# trill.net
KiCad netlist of a schematic drawn in EAGLE
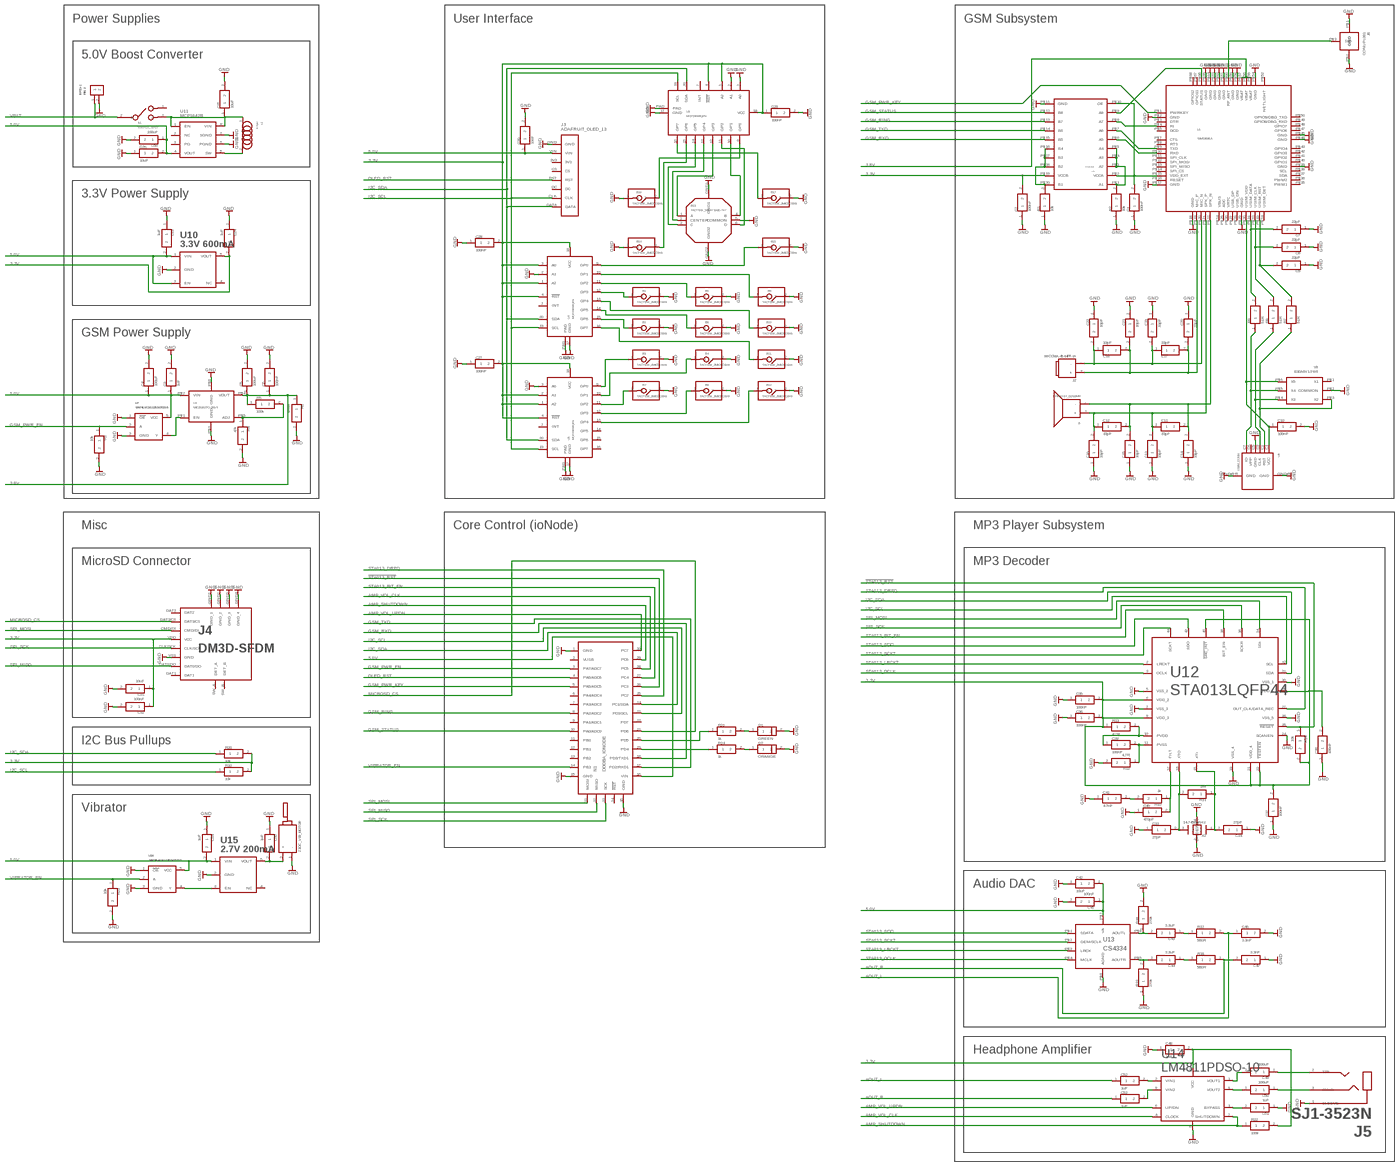
[diagram p0: schematic, sheet 1, overview]
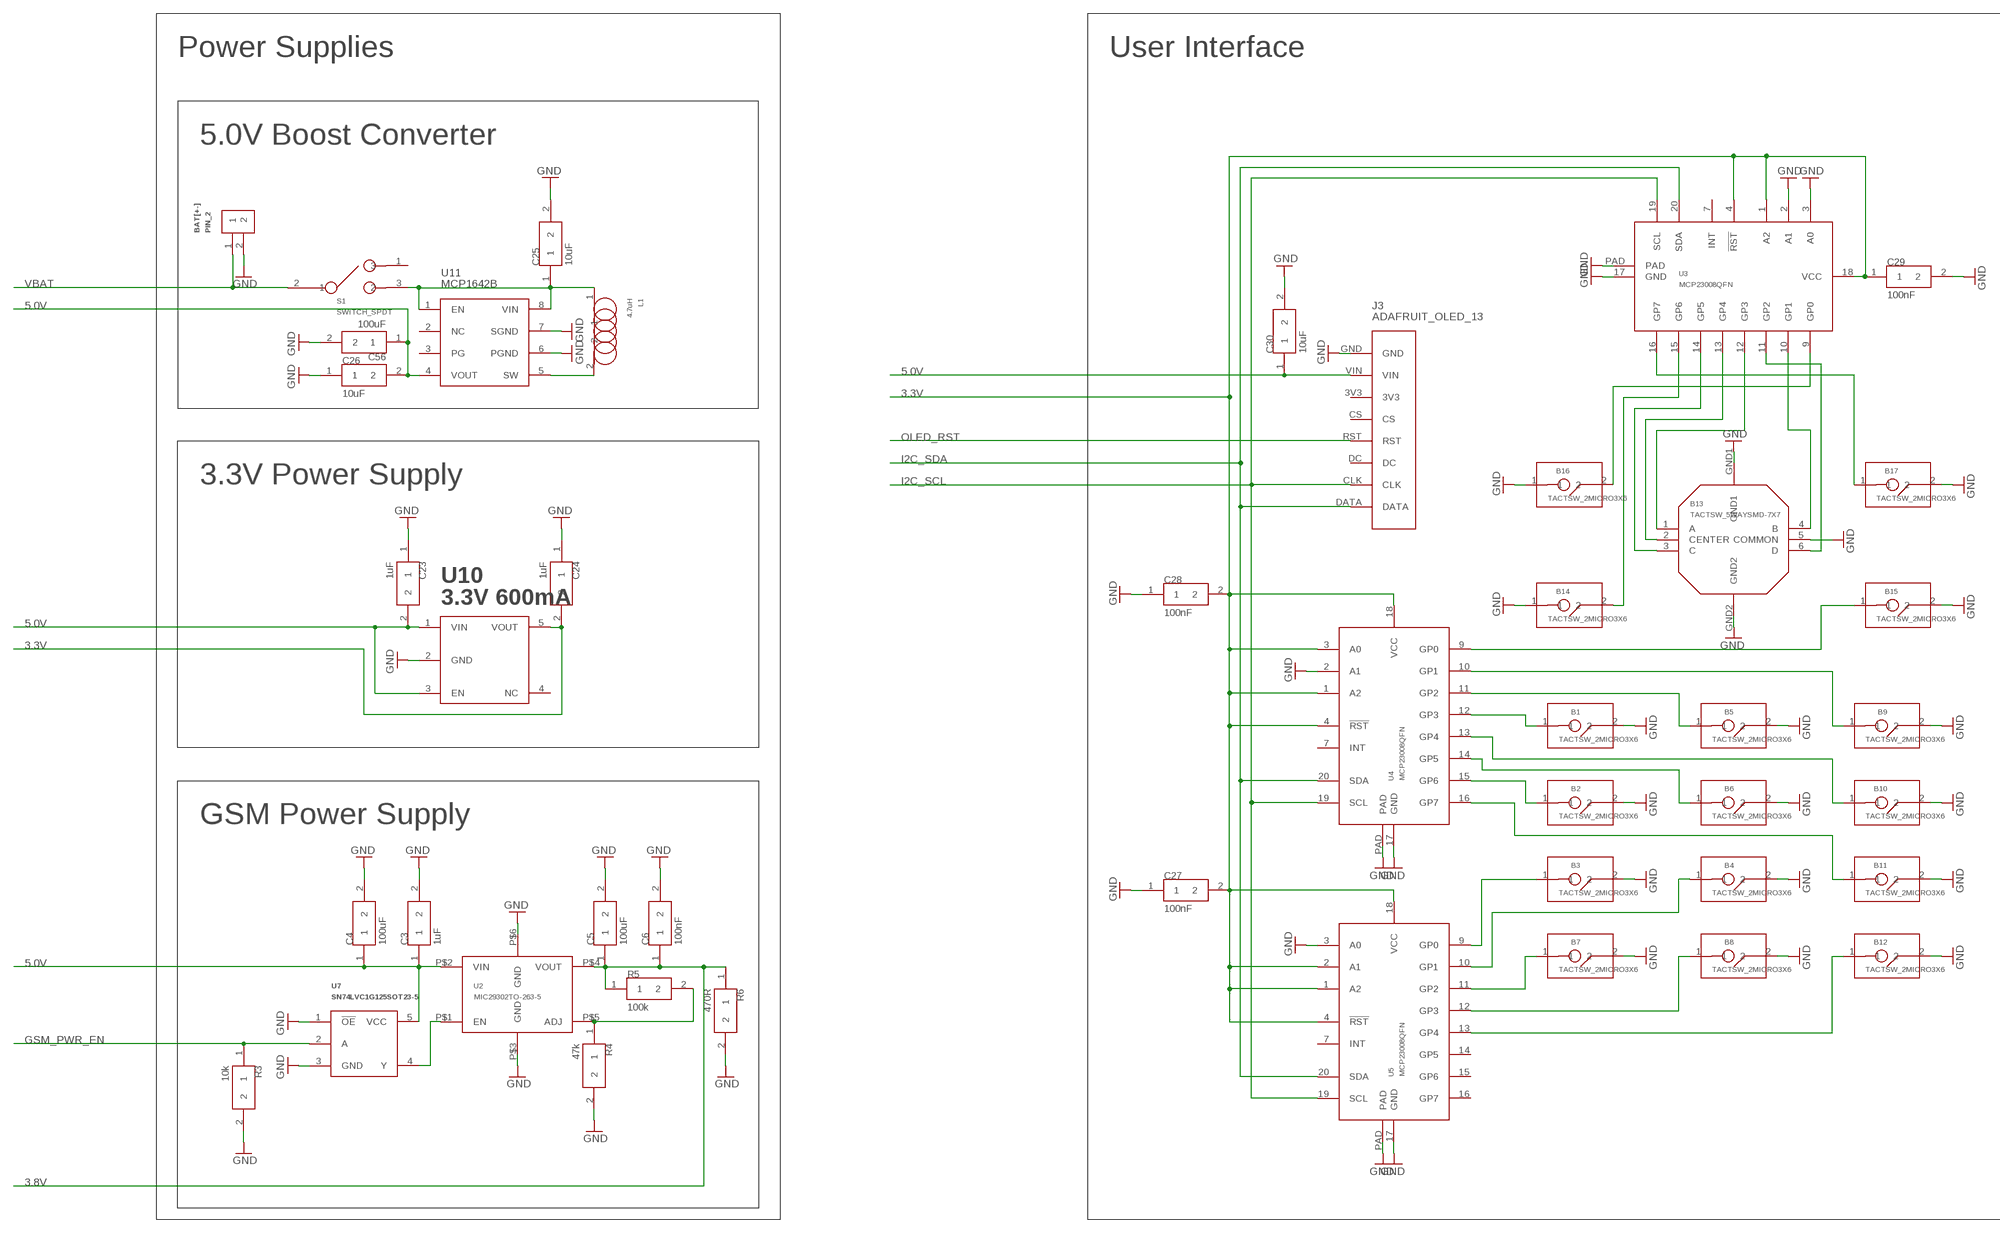
[diagram p1: schematic, sheet 1, part 1 of 4]
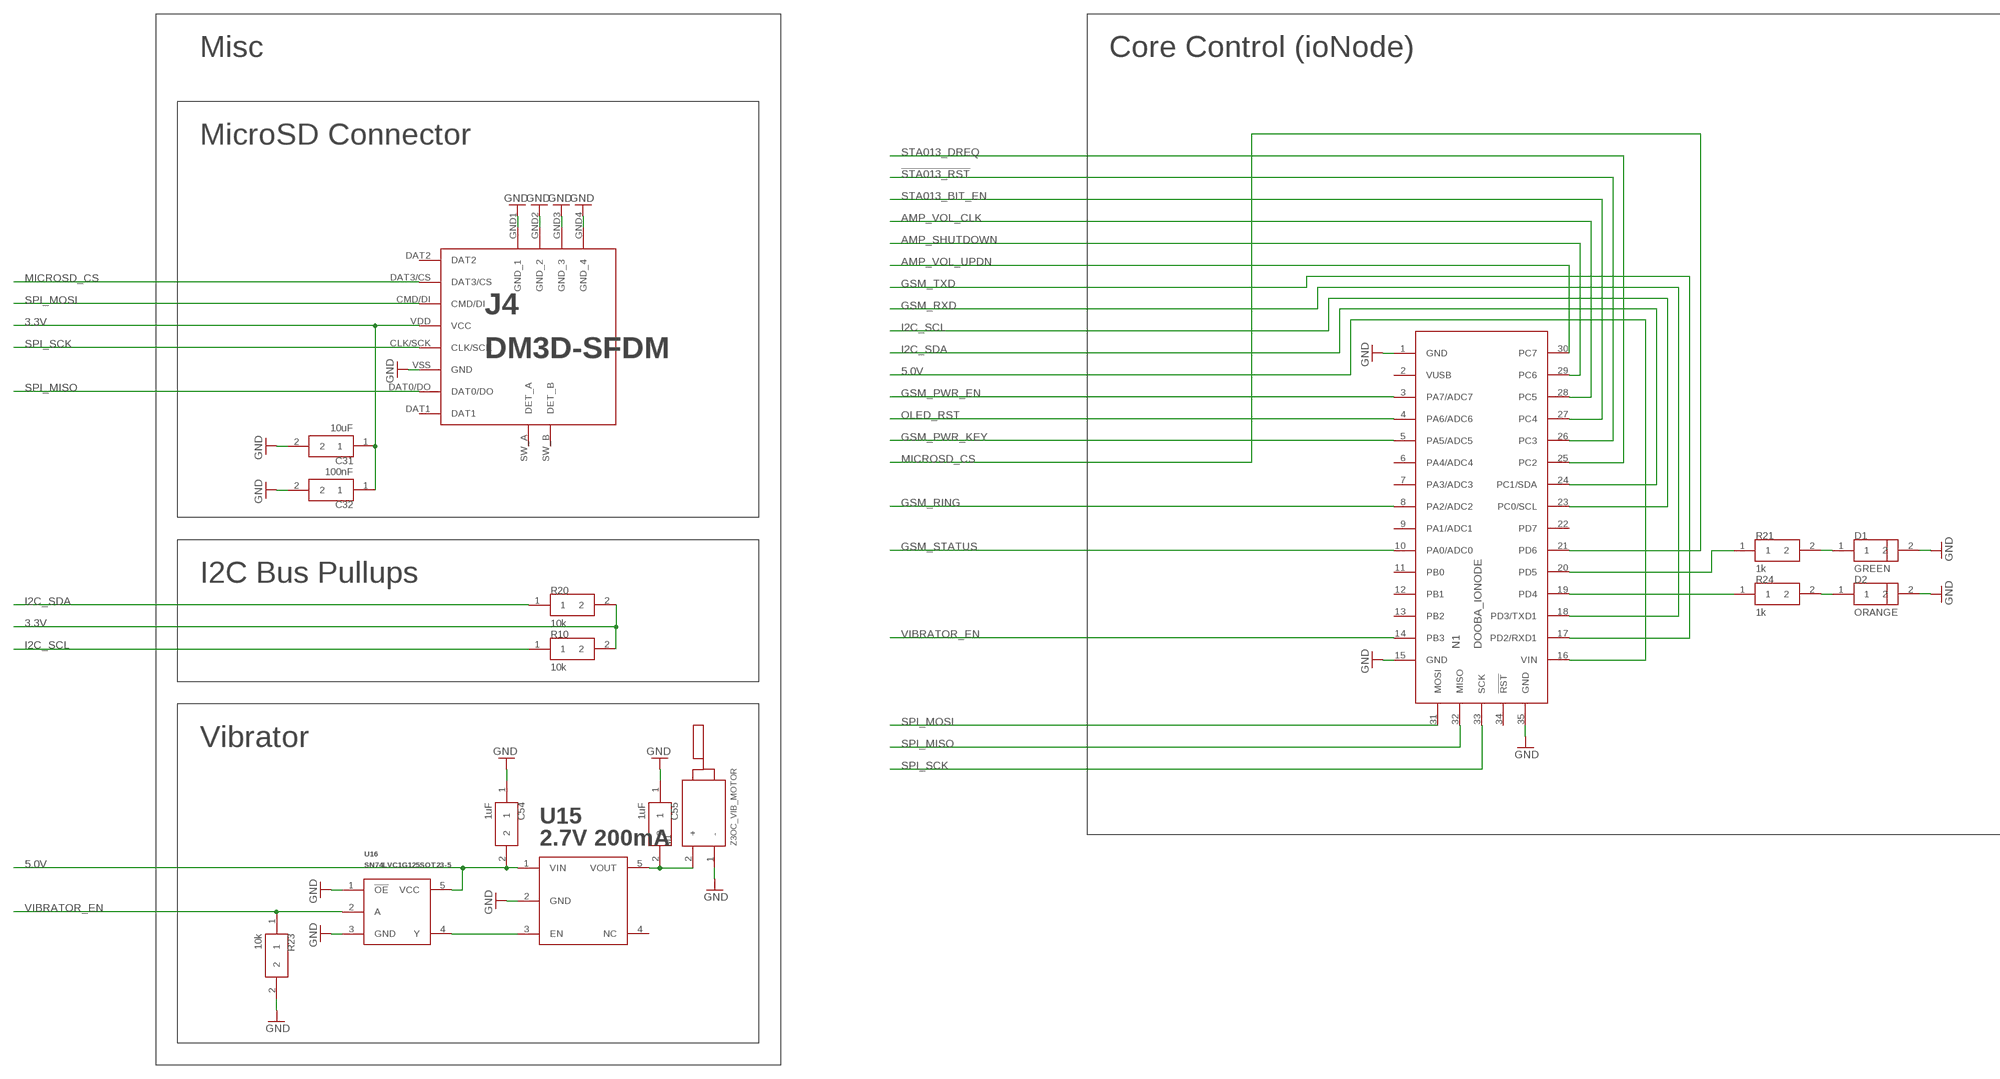
[diagram p2: schematic, sheet 1, part 2 of 4]
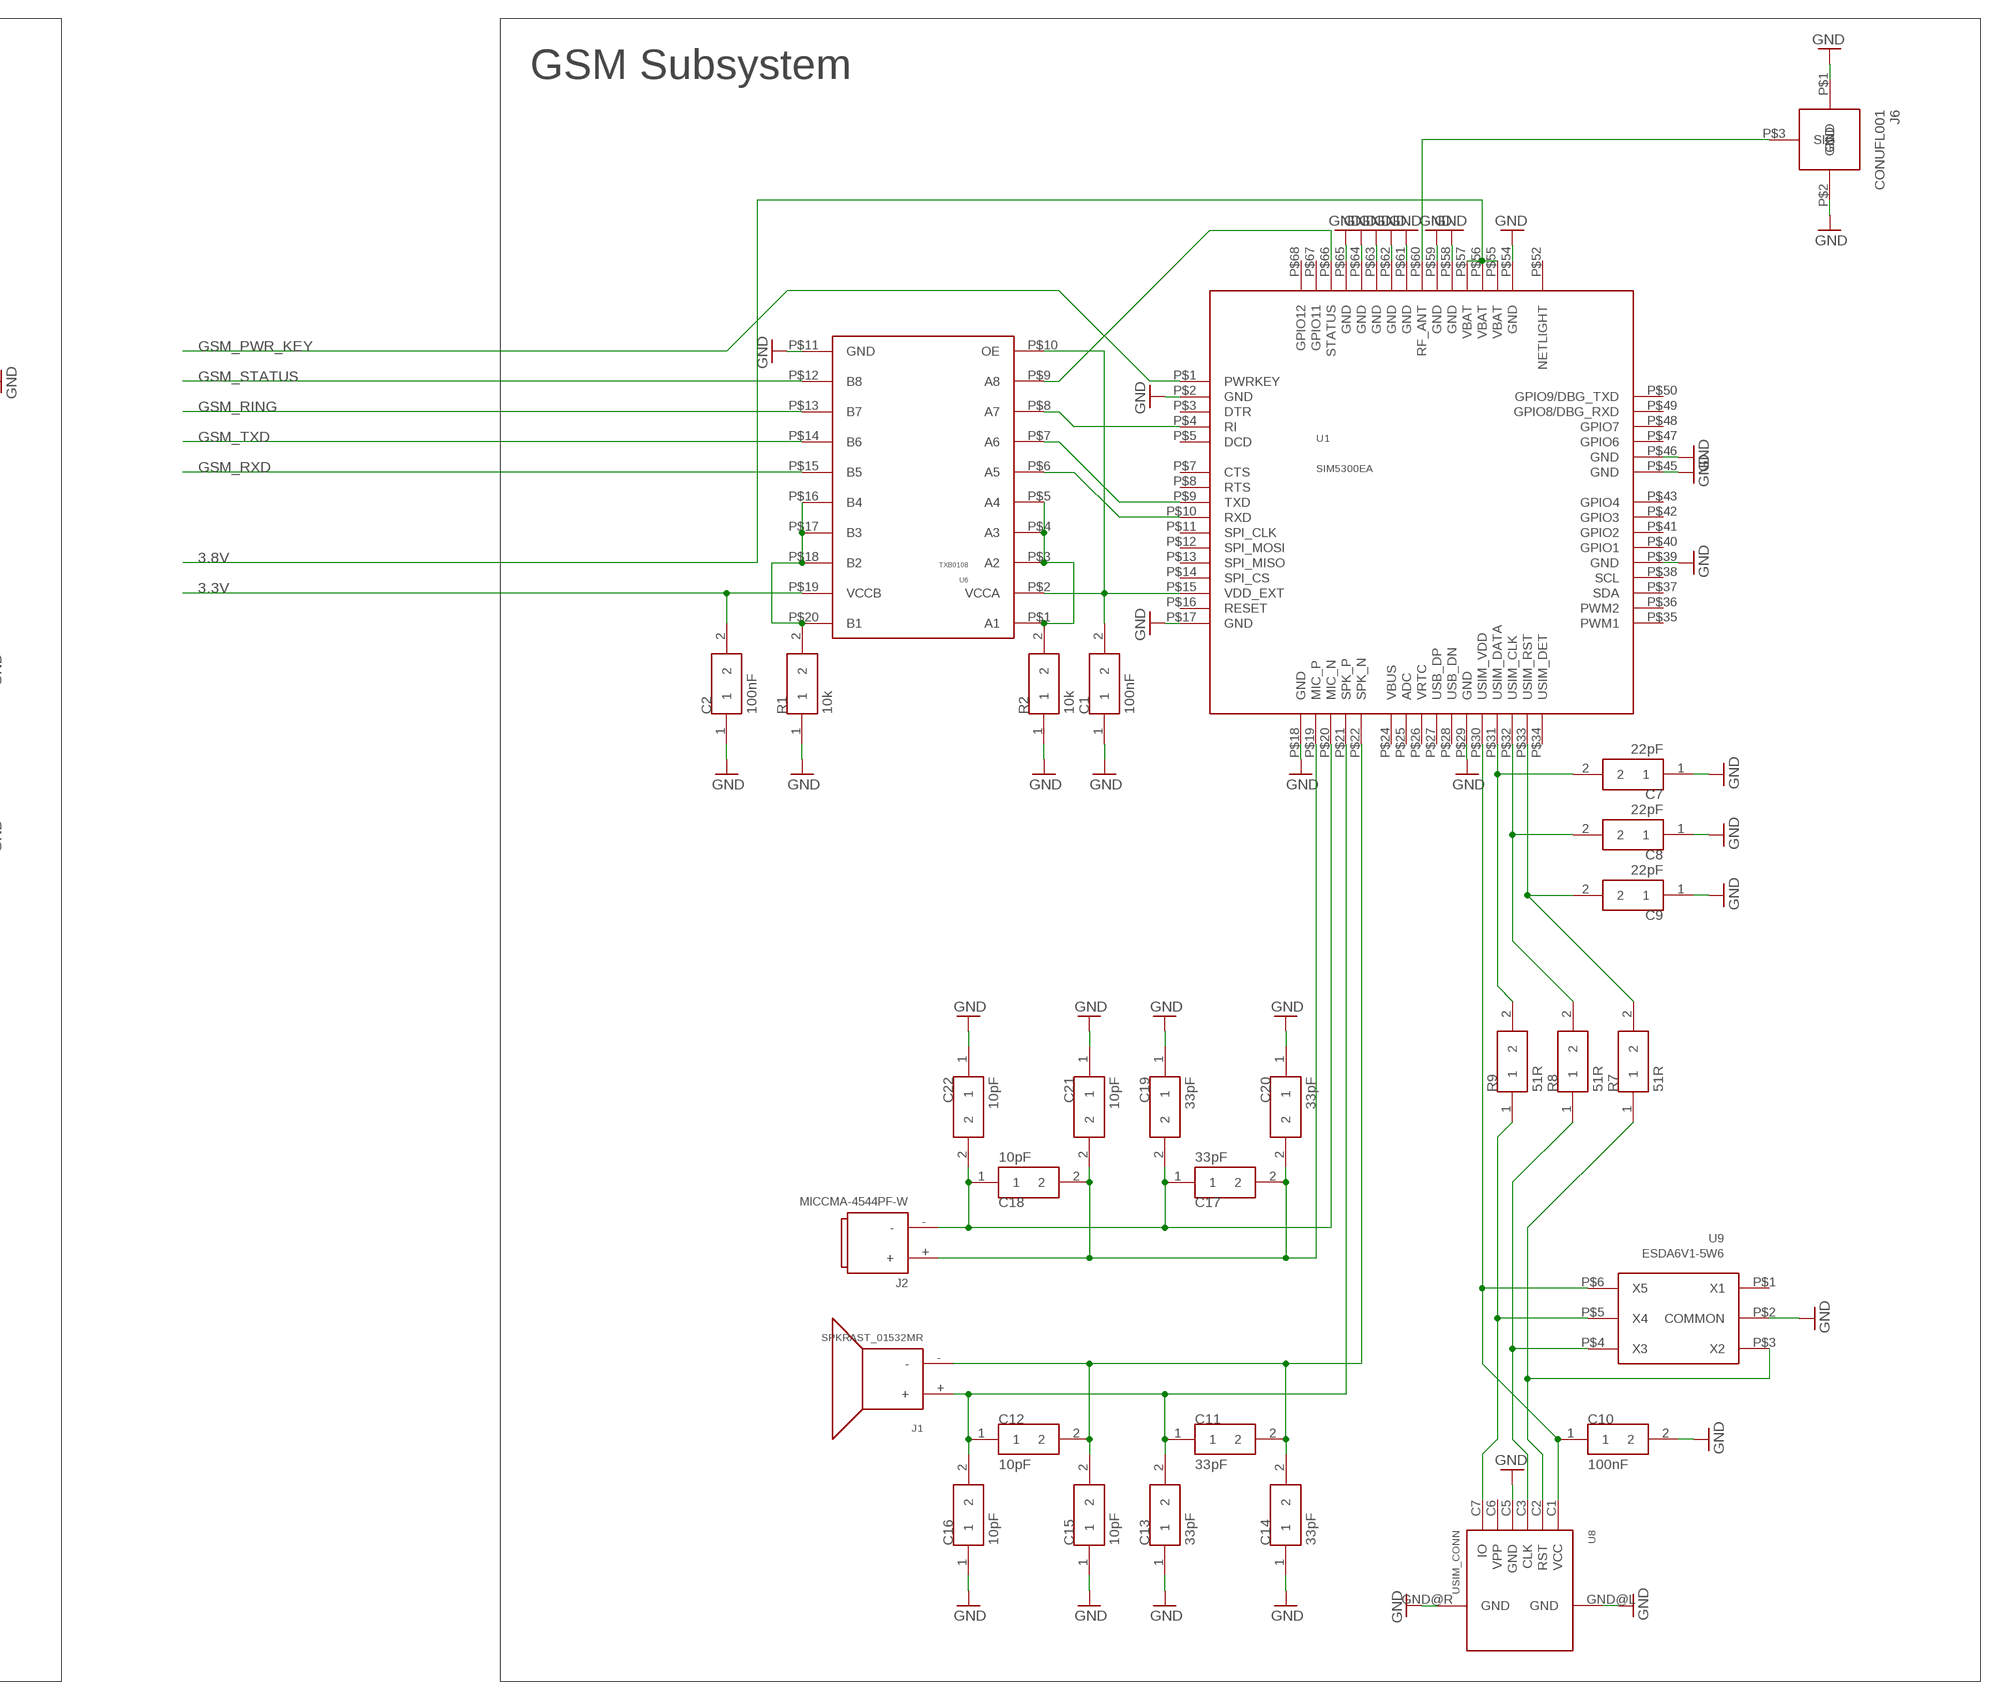
[diagram p3: schematic, sheet 1, part 3 of 4]
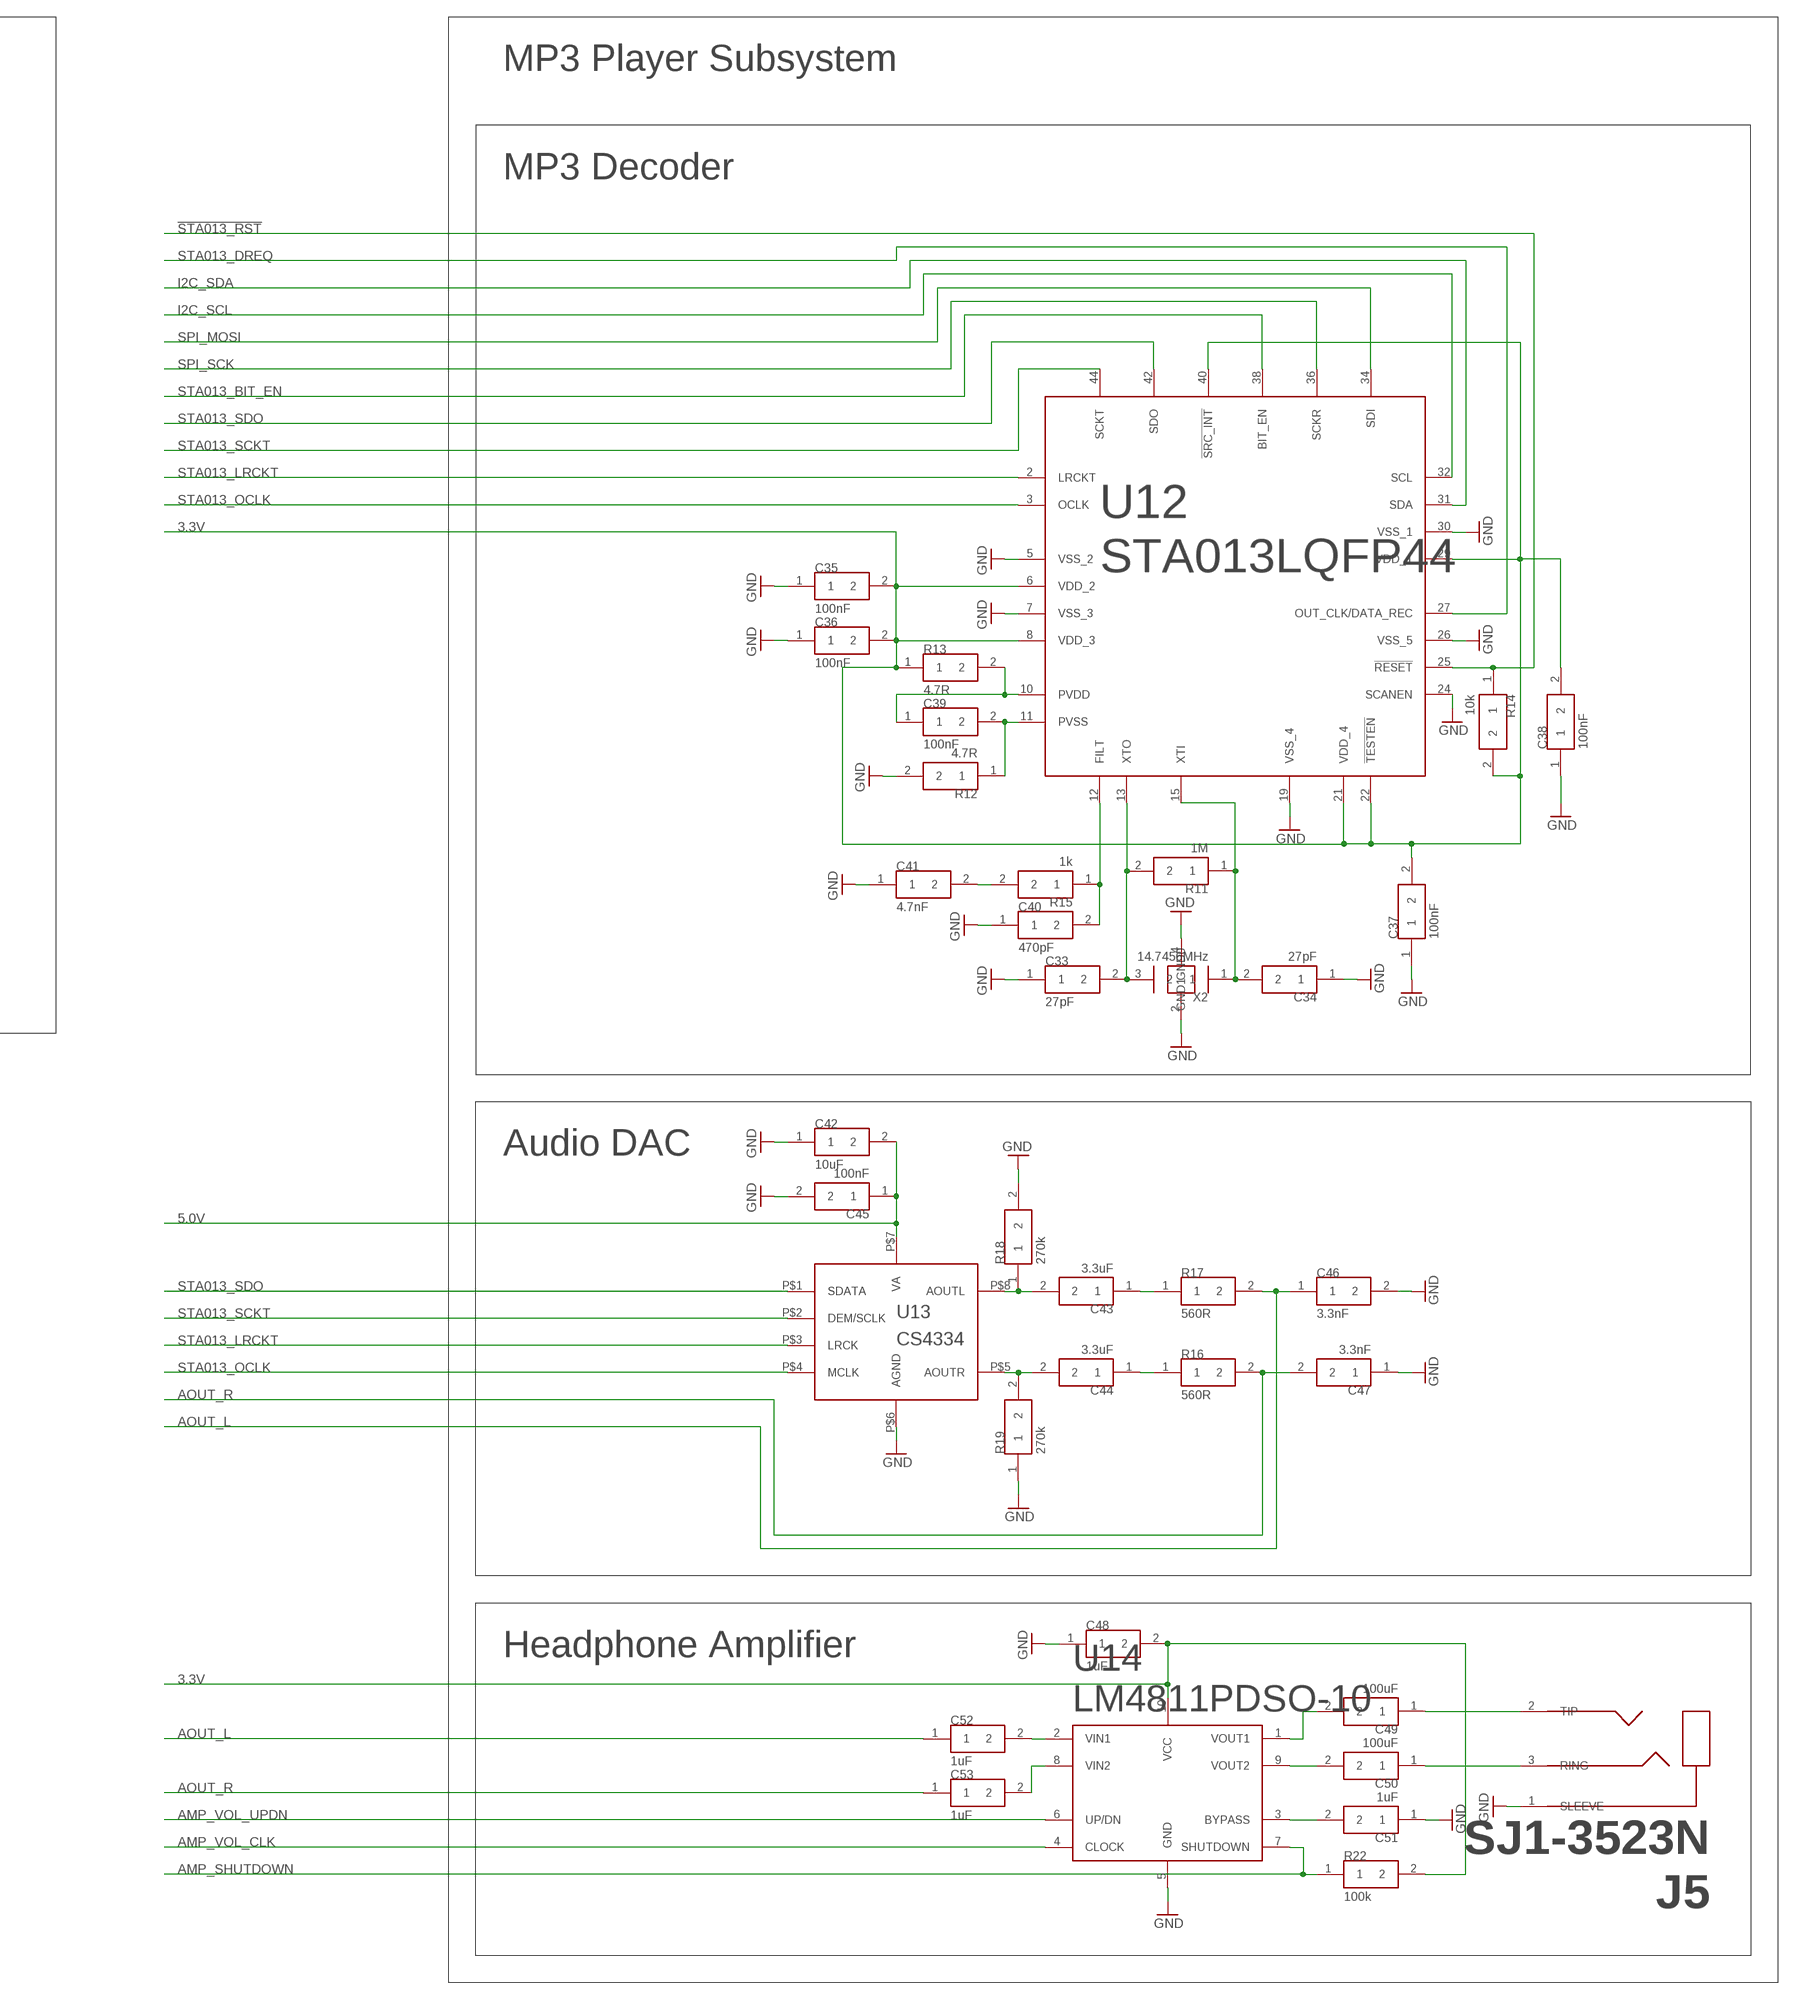
[diagram p4: schematic, sheet 1, part 4 of 4]

(export (version "E")
  (design (tool "Eeschema 10.0.6"))
  (components
    (comp (ref "B1")
      (value "TACTSW_2MICRO3X6")
      (footprint "eagle-import:TACTSW_MICRO3X6")
      (libsource (lib "eagle-import") (part "TACTSW_2MICRO3X6"))
    )
    (comp (ref "B2")
      (value "TACTSW_2MICRO3X6")
      (footprint "eagle-import:TACTSW_MICRO3X6")
      (libsource (lib "eagle-import") (part "TACTSW_2MICRO3X6"))
    )
    (comp (ref "B3")
      (value "TACTSW_2MICRO3X6")
      (footprint "eagle-import:TACTSW_MICRO3X6")
      (libsource (lib "eagle-import") (part "TACTSW_2MICRO3X6"))
    )
    (comp (ref "B4")
      (value "TACTSW_2MICRO3X6")
      (footprint "eagle-import:TACTSW_MICRO3X6")
      (libsource (lib "eagle-import") (part "TACTSW_2MICRO3X6"))
    )
    (comp (ref "B5")
      (value "TACTSW_2MICRO3X6")
      (footprint "eagle-import:TACTSW_MICRO3X6")
      (libsource (lib "eagle-import") (part "TACTSW_2MICRO3X6"))
    )
    (comp (ref "B6")
      (value "TACTSW_2MICRO3X6")
      (footprint "eagle-import:TACTSW_MICRO3X6")
      (libsource (lib "eagle-import") (part "TACTSW_2MICRO3X6"))
    )
    (comp (ref "B7")
      (value "TACTSW_2MICRO3X6")
      (footprint "eagle-import:TACTSW_MICRO3X6")
      (libsource (lib "eagle-import") (part "TACTSW_2MICRO3X6"))
    )
    (comp (ref "B8")
      (value "TACTSW_2MICRO3X6")
      (footprint "eagle-import:TACTSW_MICRO3X6")
      (libsource (lib "eagle-import") (part "TACTSW_2MICRO3X6"))
    )
    (comp (ref "B9")
      (value "TACTSW_2MICRO3X6")
      (footprint "eagle-import:TACTSW_MICRO3X6")
      (libsource (lib "eagle-import") (part "TACTSW_2MICRO3X6"))
    )
    (comp (ref "B10")
      (value "TACTSW_2MICRO3X6")
      (footprint "eagle-import:TACTSW_MICRO3X6")
      (libsource (lib "eagle-import") (part "TACTSW_2MICRO3X6"))
    )
    (comp (ref "B11")
      (value "TACTSW_2MICRO3X6")
      (footprint "eagle-import:TACTSW_MICRO3X6")
      (libsource (lib "eagle-import") (part "TACTSW_2MICRO3X6"))
    )
    (comp (ref "B12")
      (value "TACTSW_2MICRO3X6")
      (footprint "eagle-import:TACTSW_MICRO3X6")
      (libsource (lib "eagle-import") (part "TACTSW_2MICRO3X6"))
    )
    (comp (ref "B13")
      (value "TACTSW_5WAYSMD-7X7")
      (footprint "eagle-import:TACTSW-5WAY-7X7")
      (libsource (lib "eagle-import") (part "TACTSW_5WAYSMD-7X7"))
    )
    (comp (ref "B14")
      (value "TACTSW_2MICRO3X6")
      (footprint "eagle-import:TACTSW_MICRO3X6")
      (libsource (lib "eagle-import") (part "TACTSW_2MICRO3X6"))
    )
    (comp (ref "B15")
      (value "TACTSW_2MICRO3X6")
      (footprint "eagle-import:TACTSW_MICRO3X6")
      (libsource (lib "eagle-import") (part "TACTSW_2MICRO3X6"))
    )
    (comp (ref "B16")
      (value "TACTSW_2MICRO3X6")
      (footprint "eagle-import:TACTSW_MICRO3X6")
      (libsource (lib "eagle-import") (part "TACTSW_2MICRO3X6"))
    )
    (comp (ref "B17")
      (value "TACTSW_2MICRO3X6")
      (footprint "eagle-import:TACTSW_MICRO3X6")
      (libsource (lib "eagle-import") (part "TACTSW_2MICRO3X6"))
    )
    (comp (ref "BAT[+-]")
      (value "PIN_2")
      (footprint "eagle-import:PIN_2")
      (libsource (lib "eagle-import") (part "PIN_2"))
    )
    (comp (ref "C1")
      (value "100nF")
      (footprint "eagle-import:0805")
      (libsource (lib "eagle-import") (part "CAP0805"))
    )
    (comp (ref "C2")
      (value "100nF")
      (footprint "eagle-import:0805")
      (libsource (lib "eagle-import") (part "CAP0805"))
    )
    (comp (ref "C3")
      (value "1uF")
      (footprint "eagle-import:0805")
      (libsource (lib "eagle-import") (part "CAP0805"))
    )
    (comp (ref "C4")
      (value "100uF")
      (footprint "eagle-import:1210")
      (libsource (lib "eagle-import") (part "CAP1210"))
    )
    (comp (ref "C5")
      (value "100uF")
      (footprint "eagle-import:1210")
      (libsource (lib "eagle-import") (part "CAP1210"))
    )
    (comp (ref "C6")
      (value "100nF")
      (footprint "eagle-import:0805")
      (libsource (lib "eagle-import") (part "CAP0805"))
    )
    (comp (ref "C7")
      (value "22pF")
      (footprint "eagle-import:0805")
      (libsource (lib "eagle-import") (part "CAP0805"))
    )
    (comp (ref "C8")
      (value "22pF")
      (footprint "eagle-import:0805")
      (libsource (lib "eagle-import") (part "CAP0805"))
    )
    (comp (ref "C9")
      (value "22pF")
      (footprint "eagle-import:0805")
      (libsource (lib "eagle-import") (part "CAP0805"))
    )
    (comp (ref "C10")
      (value "100nF")
      (footprint "eagle-import:0805")
      (libsource (lib "eagle-import") (part "CAP0805"))
    )
    (comp (ref "C11")
      (value "33pF")
      (footprint "eagle-import:0805")
      (libsource (lib "eagle-import") (part "CAP0805"))
    )
    (comp (ref "C12")
      (value "10pF")
      (footprint "eagle-import:0805")
      (libsource (lib "eagle-import") (part "CAP0805"))
    )
    (comp (ref "C13")
      (value "33pF")
      (footprint "eagle-import:0805")
      (libsource (lib "eagle-import") (part "CAP0805"))
    )
    (comp (ref "C14")
      (value "33pF")
      (footprint "eagle-import:0805")
      (libsource (lib "eagle-import") (part "CAP0805"))
    )
    (comp (ref "C15")
      (value "10pF")
      (footprint "eagle-import:0805")
      (libsource (lib "eagle-import") (part "CAP0805"))
    )
    (comp (ref "C16")
      (value "10pF")
      (footprint "eagle-import:0805")
      (libsource (lib "eagle-import") (part "CAP0805"))
    )
    (comp (ref "C17")
      (value "33pF")
      (footprint "eagle-import:0805")
      (libsource (lib "eagle-import") (part "CAP0805"))
    )
    (comp (ref "C18")
      (value "10pF")
      (footprint "eagle-import:0805")
      (libsource (lib "eagle-import") (part "CAP0805"))
    )
    (comp (ref "C19")
      (value "33pF")
      (footprint "eagle-import:0805")
      (libsource (lib "eagle-import") (part "CAP0805"))
    )
    (comp (ref "C20")
      (value "33pF")
      (footprint "eagle-import:0805")
      (libsource (lib "eagle-import") (part "CAP0805"))
    )
    (comp (ref "C21")
      (value "10pF")
      (footprint "eagle-import:0805")
      (libsource (lib "eagle-import") (part "CAP0805"))
    )
    (comp (ref "C22")
      (value "10pF")
      (footprint "eagle-import:0805")
      (libsource (lib "eagle-import") (part "CAP0805"))
    )
    (comp (ref "C23")
      (value "1uF")
      (footprint "eagle-import:0805")
      (libsource (lib "eagle-import") (part "CAP0805"))
    )
    (comp (ref "C24")
      (value "1uF")
      (footprint "eagle-import:0805")
      (libsource (lib "eagle-import") (part "CAP0805"))
    )
    (comp (ref "C25")
      (value "10uF")
      (footprint "eagle-import:0805")
      (libsource (lib "eagle-import") (part "CAP0805"))
    )
    (comp (ref "C26")
      (value "10uF")
      (footprint "eagle-import:0805")
      (libsource (lib "eagle-import") (part "CAP0805"))
    )
    (comp (ref "C27")
      (value "100nF")
      (footprint "eagle-import:0805")
      (libsource (lib "eagle-import") (part "CAP0805"))
    )
    (comp (ref "C28")
      (value "100nF")
      (footprint "eagle-import:0805")
      (libsource (lib "eagle-import") (part "CAP0805"))
    )
    (comp (ref "C29")
      (value "100nF")
      (footprint "eagle-import:0805")
      (libsource (lib "eagle-import") (part "CAP0805"))
    )
    (comp (ref "C30")
      (value "10uF")
      (footprint "eagle-import:0805")
      (libsource (lib "eagle-import") (part "CAP0805"))
    )
    (comp (ref "C31")
      (value "10uF")
      (footprint "eagle-import:0805")
      (libsource (lib "eagle-import") (part "CAP0805"))
    )
    (comp (ref "C32")
      (value "100nF")
      (footprint "eagle-import:0805")
      (libsource (lib "eagle-import") (part "CAP0805"))
    )
    (comp (ref "C33")
      (value "27pF")
      (footprint "eagle-import:0805")
      (libsource (lib "eagle-import") (part "CAP0805"))
    )
    (comp (ref "C34")
      (value "27pF")
      (footprint "eagle-import:0805")
      (libsource (lib "eagle-import") (part "CAP0805"))
    )
    (comp (ref "C35")
      (value "100nF")
      (footprint "eagle-import:0805")
      (libsource (lib "eagle-import") (part "CAP0805"))
    )
    (comp (ref "C36")
      (value "100nF")
      (footprint "eagle-import:0805")
      (libsource (lib "eagle-import") (part "CAP0805"))
    )
    (comp (ref "C37")
      (value "100nF")
      (footprint "eagle-import:0805")
      (libsource (lib "eagle-import") (part "CAP0805"))
    )
    (comp (ref "C38")
      (value "100nF")
      (footprint "eagle-import:0805")
      (libsource (lib "eagle-import") (part "CAP0805"))
    )
    (comp (ref "C39")
      (value "100nF")
      (footprint "eagle-import:0805")
      (libsource (lib "eagle-import") (part "CAP0805"))
    )
    (comp (ref "C40")
      (value "470pF")
      (footprint "eagle-import:0805")
      (libsource (lib "eagle-import") (part "CAP0805"))
    )
    (comp (ref "C41")
      (value "4.7nF")
      (footprint "eagle-import:0805")
      (libsource (lib "eagle-import") (part "CAP0805"))
    )
    (comp (ref "C42")
      (value "10uF")
      (footprint "eagle-import:0805")
      (libsource (lib "eagle-import") (part "CAP0805"))
    )
    (comp (ref "C43")
      (value "3.3uF")
      (footprint "eagle-import:0805")
      (libsource (lib "eagle-import") (part "CAP0805"))
    )
    (comp (ref "C44")
      (value "3.3uF")
      (footprint "eagle-import:0805")
      (libsource (lib "eagle-import") (part "CAP0805"))
    )
    (comp (ref "C45")
      (value "100nF")
      (footprint "eagle-import:0805")
      (libsource (lib "eagle-import") (part "CAP0805"))
    )
    (comp (ref "C46")
      (value "3.3nF")
      (footprint "eagle-import:0805")
      (libsource (lib "eagle-import") (part "CAP0805"))
    )
    (comp (ref "C47")
      (value "3.3nF")
      (footprint "eagle-import:0805")
      (libsource (lib "eagle-import") (part "CAP0805"))
    )
    (comp (ref "C48")
      (value "1uF")
      (footprint "eagle-import:0805")
      (libsource (lib "eagle-import") (part "CAP0805"))
    )
    (comp (ref "C49")
      (value "100uF")
      (footprint "eagle-import:1210")
      (libsource (lib "eagle-import") (part "CAP1210"))
    )
    (comp (ref "C50")
      (value "100uF")
      (footprint "eagle-import:1210")
      (libsource (lib "eagle-import") (part "CAP1210"))
    )
    (comp (ref "C51")
      (value "1uF")
      (footprint "eagle-import:0805")
      (libsource (lib "eagle-import") (part "CAP0805"))
    )
    (comp (ref "C52")
      (value "1uF")
      (footprint "eagle-import:0805")
      (libsource (lib "eagle-import") (part "CAP0805"))
    )
    (comp (ref "C53")
      (value "1uF")
      (footprint "eagle-import:0805")
      (libsource (lib "eagle-import") (part "CAP0805"))
    )
    (comp (ref "C54")
      (value "1uF")
      (footprint "eagle-import:0805")
      (libsource (lib "eagle-import") (part "CAP0805"))
    )
    (comp (ref "C55")
      (value "1uF")
      (footprint "eagle-import:0805")
      (libsource (lib "eagle-import") (part "CAP0805"))
    )
    (comp (ref "C56")
      (value "100uF")
      (footprint "eagle-import:1210")
      (libsource (lib "eagle-import") (part "CAP1210"))
    )
    (comp (ref "D1")
      (value "GREEN")
      (footprint "eagle-import:0805")
      (libsource (lib "eagle-import") (part "LED0805"))
    )
    (comp (ref "D2")
      (value "ORANGE")
      (footprint "eagle-import:0805")
      (libsource (lib "eagle-import") (part "LED0805"))
    )
    (comp (ref "J1")
      (value "SPKRAST_01532MR")
      (footprint "eagle-import:SPKR_AST_01532MR")
      (libsource (lib "eagle-import") (part "SPKRAST_01532MR"))
    )
    (comp (ref "J2")
      (value "MICCMA-4544PF-W")
      (footprint "eagle-import:MIC_CMA-4544PF-W")
      (libsource (lib "eagle-import") (part "MICCMA-4544PF-W"))
    )
    (comp (ref "J3")
      (value "ADAFRUIT_OLED_13")
      (footprint "eagle-import:ADAFRUIT_OLED_13")
      (libsource (lib "eagle-import") (part "ADAFRUIT_OLED_13"))
    )
    (comp (ref "J4")
      (value "DM3D-SFDM")
      (footprint "eagle-import:DM3D-SF")
      (libsource (lib "eagle-import") (part "DM3D-SFDM"))
    )
    (comp (ref "J5")
      (value "SJ1-3523N")
      (footprint "eagle-import:SJ1-352XN")
      (libsource (lib "eagle-import") (part "SJ1-3523N"))
    )
    (comp (ref "J6")
      (value "CONUFL001")
      (footprint "eagle-import:CONUFL001")
      (libsource (lib "eagle-import") (part "CONUFL001"))
    )
    (comp (ref "L1")
      (value "4.7uH")
      (footprint "eagle-import:2520")
      (libsource (lib "eagle-import") (part "IND2520"))
    )
    (comp (ref "M1")
      (value "Z3OC_VIB_MOTOR")
      (footprint "eagle-import:Z3OC_VIB_MOTOR")
      (libsource (lib "eagle-import") (part "Z3OC_VIB_MOTOR"))
    )
    (comp (ref "N1")
      (value "DOOBA_IONODE")
      (footprint "eagle-import:DOOBA_IONODE")
      (libsource (lib "eagle-import") (part "DOOBA_IONODE"))
    )
    (comp (ref "R1")
      (value "10k")
      (footprint "eagle-import:0805")
      (libsource (lib "eagle-import") (part "RES0805"))
    )
    (comp (ref "R2")
      (value "10k")
      (footprint "eagle-import:0805")
      (libsource (lib "eagle-import") (part "RES0805"))
    )
    (comp (ref "R3")
      (value "10k")
      (footprint "eagle-import:0805")
      (libsource (lib "eagle-import") (part "RES0805"))
    )
    (comp (ref "R4")
      (value "47k")
      (footprint "eagle-import:0805")
      (libsource (lib "eagle-import") (part "RES0805"))
    )
    (comp (ref "R5")
      (value "100k")
      (footprint "eagle-import:0805")
      (libsource (lib "eagle-import") (part "RES0805"))
    )
    (comp (ref "R6")
      (value "470R")
      (footprint "eagle-import:0805")
      (libsource (lib "eagle-import") (part "RES0805"))
    )
    (comp (ref "R7")
      (value "51R")
      (footprint "eagle-import:0805")
      (libsource (lib "eagle-import") (part "RES0805"))
    )
    (comp (ref "R8")
      (value "51R")
      (footprint "eagle-import:0805")
      (libsource (lib "eagle-import") (part "RES0805"))
    )
    (comp (ref "R9")
      (value "51R")
      (footprint "eagle-import:0805")
      (libsource (lib "eagle-import") (part "RES0805"))
    )
    (comp (ref "R10")
      (value "10k")
      (footprint "eagle-import:0805")
      (libsource (lib "eagle-import") (part "RES0805"))
    )
    (comp (ref "R11")
      (value "1M")
      (footprint "eagle-import:0805")
      (libsource (lib "eagle-import") (part "RES0805"))
    )
    (comp (ref "R12")
      (value "4.7R")
      (footprint "eagle-import:0805")
      (libsource (lib "eagle-import") (part "RES0805"))
    )
    (comp (ref "R13")
      (value "4.7R")
      (footprint "eagle-import:0805")
      (libsource (lib "eagle-import") (part "RES0805"))
    )
    (comp (ref "R14")
      (value "10k")
      (footprint "eagle-import:0805")
      (libsource (lib "eagle-import") (part "RES0805"))
    )
    (comp (ref "R15")
      (value "1k")
      (footprint "eagle-import:0805")
      (libsource (lib "eagle-import") (part "RES0805"))
    )
    (comp (ref "R16")
      (value "560R")
      (footprint "eagle-import:0805")
      (libsource (lib "eagle-import") (part "RES0805"))
    )
    (comp (ref "R17")
      (value "560R")
      (footprint "eagle-import:0805")
      (libsource (lib "eagle-import") (part "RES0805"))
    )
    (comp (ref "R18")
      (value "270k")
      (footprint "eagle-import:0805")
      (libsource (lib "eagle-import") (part "RES0805"))
    )
    (comp (ref "R19")
      (value "270k")
      (footprint "eagle-import:0805")
      (libsource (lib "eagle-import") (part "RES0805"))
    )
    (comp (ref "R20")
      (value "10k")
      (footprint "eagle-import:0805")
      (libsource (lib "eagle-import") (part "RES0805"))
    )
    (comp (ref "R21")
      (value "1k")
      (footprint "eagle-import:0805")
      (libsource (lib "eagle-import") (part "RES0805"))
    )
    (comp (ref "R22")
      (value "100k")
      (footprint "eagle-import:0805")
      (libsource (lib "eagle-import") (part "RES0805"))
    )
    (comp (ref "R23")
      (value "10k")
      (footprint "eagle-import:0805")
      (libsource (lib "eagle-import") (part "RES0805"))
    )
    (comp (ref "R24")
      (value "1k")
      (footprint "eagle-import:0805")
      (libsource (lib "eagle-import") (part "RES0805"))
    )
    (comp (ref "S1")
      (value "SWITCH_SPDT")
      (footprint "eagle-import:JS102011")
      (libsource (lib "eagle-import") (part "SWITCH_SPDT"))
    )
    (comp (ref "U1")
      (value "SIM5300EA")
      (footprint "eagle-import:SIM5300")
      (libsource (lib "eagle-import") (part "SIM5300EA"))
    )
    (comp (ref "U2")
      (value "MIC29302TO-263-5")
      (footprint "eagle-import:TO-263")
      (libsource (lib "eagle-import") (part "MIC29302TO-263-5"))
    )
    (comp (ref "U3")
      (value "MCP23008QFN")
      (footprint "eagle-import:20-VQFN")
      (libsource (lib "eagle-import") (part "MCP23008QFN"))
    )
    (comp (ref "U4")
      (value "MCP23008QFN")
      (footprint "eagle-import:20-VQFN")
      (libsource (lib "eagle-import") (part "MCP23008QFN"))
    )
    (comp (ref "U5")
      (value "MCP23008QFN")
      (footprint "eagle-import:20-VQFN")
      (libsource (lib "eagle-import") (part "MCP23008QFN"))
    )
    (comp (ref "U6")
      (value "TXB0108")
      (footprint "eagle-import:TSSOP-20")
      (libsource (lib "eagle-import") (part "TXB0108"))
    )
    (comp (ref "U7")
      (value "SN74LVC1G125SOT23-5")
      (footprint "eagle-import:SOT23-5")
      (libsource (lib "eagle-import") (part "SN74LVC1G125SOT23-5"))
    )
    (comp (ref "U8")
      (value "USIM_CONN")
      (footprint "eagle-import:WE_USIM_HINGE")
      (libsource (lib "eagle-import") (part "USIM_CONN"))
    )
    (comp (ref "U9")
      (value "ESDA6V1-5W6")
      (footprint "eagle-import:SOT-323-6L")
      (libsource (lib "eagle-import") (part "ESDA6V1-5W6"))
    )
    (comp (ref "U10")
      (value "3.3V 600mA")
      (footprint "eagle-import:SOT23-5")
      (libsource (lib "eagle-import") (part "LP3985SOT23-5"))
    )
    (comp (ref "U11")
      (value "MCP1642B")
      (footprint "eagle-import:MSOP8")
      (libsource (lib "eagle-import") (part "MCP1642B"))
    )
    (comp (ref "U12")
      (value "STA013LQFP44")
      (footprint "eagle-import:QFP44")
      (libsource (lib "eagle-import") (part "STA013LQFP44"))
    )
    (comp (ref "U13")
      (value "CS4334")
      (footprint "eagle-import:SO8")
      (libsource (lib "eagle-import") (part "CS4334"))
    )
    (comp (ref "U14")
      (value "LM4811PDSO-10")
      (footprint "eagle-import:PDSO-10")
      (libsource (lib "eagle-import") (part "LM4811PDSO-10"))
    )
    (comp (ref "U15")
      (value "2.7V 200mA")
      (footprint "eagle-import:SOT23-5")
      (libsource (lib "eagle-import") (part "LP3985SOT23-5"))
    )
    (comp (ref "U16")
      (value "SN74LVC1G125SOT23-5")
      (footprint "eagle-import:SOT23-5")
      (libsource (lib "eagle-import") (part "SN74LVC1G125SOT23-5"))
    )
    (comp (ref "X2")
      (value "14.7456MHz")
      (footprint "eagle-import:XTAL_3225")
      (libsource (lib "eagle-import") (part "XTAL_GNDSMD_3225"))
    )
  )
  (nets
    (net (code "1") (name "/3.3V") (class "Default")
      (node (ref "C2") (pin "2") (pinfunction "2_2") (pintype "bidirectional"))
      (node (ref "C24") (pin "2") (pinfunction "2_2") (pintype "bidirectional"))
      (node (ref "C27") (pin "2") (pinfunction "2_2") (pintype "bidirectional"))
      (node (ref "C28") (pin "2") (pinfunction "2_2") (pintype "bidirectional"))
      (node (ref "C29") (pin "1") (pinfunction "1_1") (pintype "bidirectional"))
      (node (ref "C31") (pin "1") (pinfunction "1_1") (pintype "bidirectional"))
      (node (ref "C32") (pin "1") (pinfunction "1_1") (pintype "bidirectional"))
      (node (ref "C35") (pin "2") (pinfunction "2_2") (pintype "bidirectional"))
      (node (ref "C36") (pin "2") (pinfunction "2_2") (pintype "bidirectional"))
      (node (ref "C37") (pin "2") (pinfunction "2_2") (pintype "bidirectional"))
      (node (ref "C38") (pin "2") (pinfunction "2_2") (pintype "bidirectional"))
      (node (ref "C48") (pin "2") (pinfunction "2_2") (pintype "bidirectional"))
      (node (ref "J4") (pin "VDD") (pinfunction "VCC_VDD") (pintype "bidirectional"))
      (node (ref "R10") (pin "2") (pinfunction "2_2") (pintype "bidirectional"))
      (node (ref "R13") (pin "1") (pinfunction "1_1") (pintype "bidirectional"))
      (node (ref "R14") (pin "2") (pinfunction "2_2") (pintype "bidirectional"))
      (node (ref "R20") (pin "2") (pinfunction "2_2") (pintype "bidirectional"))
      (node (ref "R22") (pin "2") (pinfunction "2_2") (pintype "bidirectional"))
      (node (ref "U10") (pin "5") (pinfunction "VOUT_5") (pintype "bidirectional"))
      (node (ref "U12") (pin "21") (pinfunction "VDD_4_21") (pintype "bidirectional"))
      (node (ref "U12") (pin "22") (pinfunction "~{TESTEN}_22") (pintype "bidirectional"))
      (node (ref "U12") (pin "29") (pinfunction "VDD_1_29") (pintype "bidirectional"))
      (node (ref "U12") (pin "40") (pinfunction "~{SRC_INT}_40") (pintype "bidirectional"))
      (node (ref "U12") (pin "6") (pinfunction "VDD_2_6") (pintype "bidirectional"))
      (node (ref "U12") (pin "8") (pinfunction "VDD_3_8") (pintype "bidirectional"))
      (node (ref "U14") (pin "10") (pinfunction "VCC_10") (pintype "bidirectional"))
      (node (ref "U3") (pin "1") (pinfunction "A2_1") (pintype "bidirectional"))
      (node (ref "U3") (pin "18") (pinfunction "VCC_18") (pintype "bidirectional"))
      (node (ref "U3") (pin "4") (pinfunction "~{RST}_4") (pintype "bidirectional"))
      (node (ref "U4") (pin "1") (pinfunction "A2_1") (pintype "bidirectional"))
      (node (ref "U4") (pin "18") (pinfunction "VCC_18") (pintype "bidirectional"))
      (node (ref "U4") (pin "3") (pinfunction "A0_3") (pintype "bidirectional"))
      (node (ref "U4") (pin "4") (pinfunction "~{RST}_4") (pintype "bidirectional"))
      (node (ref "U5") (pin "1") (pinfunction "A2_1") (pintype "bidirectional"))
      (node (ref "U5") (pin "18") (pinfunction "VCC_18") (pintype "bidirectional"))
      (node (ref "U5") (pin "2") (pinfunction "A1_2") (pintype "bidirectional"))
      (node (ref "U5") (pin "4") (pinfunction "~{RST}_4") (pintype "bidirectional"))
      (node (ref "U6") (pin "P$19") (pinfunction "VCCB_P$19") (pintype "bidirectional"))
    )
    (net (code "2") (name "/3.8V") (class "Default")
      (node (ref "C5") (pin "1") (pinfunction "1_1") (pintype "bidirectional"))
      (node (ref "C6") (pin "1") (pinfunction "1_1") (pintype "bidirectional"))
      (node (ref "R5") (pin "1") (pinfunction "1_1") (pintype "bidirectional"))
      (node (ref "R6") (pin "1") (pinfunction "1_1") (pintype "bidirectional"))
      (node (ref "U1") (pin "P$55") (pinfunction "VBAT_P$55") (pintype "bidirectional"))
      (node (ref "U1") (pin "P$56") (pinfunction "VBAT_P$56") (pintype "bidirectional"))
      (node (ref "U1") (pin "P$57") (pinfunction "VBAT_P$57") (pintype "bidirectional"))
      (node (ref "U2") (pin "P$4") (pinfunction "VOUT_P$4") (pintype "bidirectional"))
    )
    (net (code "3") (name "/5.0V") (class "Default")
      (node (ref "C23") (pin "2") (pinfunction "2_2") (pintype "bidirectional"))
      (node (ref "C26") (pin "2") (pinfunction "2_2") (pintype "bidirectional"))
      (node (ref "C3") (pin "1") (pinfunction "1_1") (pintype "bidirectional"))
      (node (ref "C30") (pin "1") (pinfunction "1_1") (pintype "bidirectional"))
      (node (ref "C4") (pin "1") (pinfunction "1_1") (pintype "bidirectional"))
      (node (ref "C42") (pin "2") (pinfunction "2_2") (pintype "bidirectional"))
      (node (ref "C45") (pin "1") (pinfunction "1_1") (pintype "bidirectional"))
      (node (ref "C54") (pin "2") (pinfunction "2_2") (pintype "bidirectional"))
      (node (ref "C56") (pin "1") (pinfunction "1_1") (pintype "bidirectional"))
      (node (ref "J3") (pin "VIN") (pinfunction "VIN_VIN") (pintype "bidirectional"))
      (node (ref "N1") (pin "16") (pinfunction "VIN_16") (pintype "bidirectional"))
      (node (ref "U10") (pin "1") (pinfunction "VIN_1") (pintype "bidirectional"))
      (node (ref "U10") (pin "3") (pinfunction "EN_3") (pintype "bidirectional"))
      (node (ref "U11") (pin "4") (pinfunction "VOUT_4") (pintype "bidirectional"))
      (node (ref "U13") (pin "P$7") (pinfunction "VA_P$7") (pintype "bidirectional"))
      (node (ref "U15") (pin "1") (pinfunction "VIN_1") (pintype "bidirectional"))
      (node (ref "U16") (pin "5") (pinfunction "VCC_5") (pintype "bidirectional"))
      (node (ref "U2") (pin "P$2") (pinfunction "VIN_P$2") (pintype "bidirectional"))
      (node (ref "U7") (pin "5") (pinfunction "VCC_5") (pintype "bidirectional"))
    )
    (net (code "4") (name "/AMP_SHUTDOWN") (class "Default")
      (node (ref "N1") (pin "29") (pinfunction "PC6_29") (pintype "bidirectional"))
      (node (ref "R22") (pin "1") (pinfunction "1_1") (pintype "bidirectional"))
      (node (ref "U14") (pin "7") (pinfunction "SHUTDOWN_7") (pintype "bidirectional"))
    )
    (net (code "5") (name "/AMP_VOL_CLK") (class "Default")
      (node (ref "N1") (pin "28") (pinfunction "PC5_28") (pintype "bidirectional"))
      (node (ref "U14") (pin "4") (pinfunction "CLOCK_4") (pintype "bidirectional"))
    )
    (net (code "6") (name "/AMP_VOL_UPDN") (class "Default")
      (node (ref "N1") (pin "30") (pinfunction "PC7_30") (pintype "bidirectional"))
      (node (ref "U14") (pin "6") (pinfunction "UP/DN_6") (pintype "bidirectional"))
    )
    (net (code "7") (name "/AOUT_L") (class "Default")
      (node (ref "C46") (pin "1") (pinfunction "1_1") (pintype "bidirectional"))
      (node (ref "C52") (pin "1") (pinfunction "1_1") (pintype "bidirectional"))
      (node (ref "R17") (pin "2") (pinfunction "2_2") (pintype "bidirectional"))
    )
    (net (code "8") (name "/AOUT_R") (class "Default")
      (node (ref "C47") (pin "2") (pinfunction "2_2") (pintype "bidirectional"))
      (node (ref "C53") (pin "1") (pinfunction "1_1") (pintype "bidirectional"))
      (node (ref "R16") (pin "2") (pinfunction "2_2") (pintype "bidirectional"))
    )
    (net (code "9") (name "/GSM_PWR_EN") (class "Default")
      (node (ref "N1") (pin "3") (pinfunction "PA7/ADC7_3") (pintype "bidirectional"))
      (node (ref "R3") (pin "1") (pinfunction "1_1") (pintype "bidirectional"))
      (node (ref "U7") (pin "2") (pinfunction "A_2") (pintype "bidirectional"))
    )
    (net (code "10") (name "/GSM_PWR_KEY") (class "Default")
      (node (ref "N1") (pin "5") (pinfunction "PA5/ADC5_5") (pintype "bidirectional"))
      (node (ref "U1") (pin "P$1") (pinfunction "PWRKEY_P$1") (pintype "bidirectional"))
    )
    (net (code "11") (name "/GSM_RING") (class "Default")
      (node (ref "N1") (pin "8") (pinfunction "PA2/ADC2_8") (pintype "bidirectional"))
      (node (ref "U6") (pin "P$13") (pinfunction "B7_P$13") (pintype "bidirectional"))
    )
    (net (code "12") (name "/GSM_RXD") (class "Default")
      (node (ref "N1") (pin "18") (pinfunction "PD3/TXD1_18") (pintype "bidirectional"))
      (node (ref "U6") (pin "P$15") (pinfunction "B5_P$15") (pintype "bidirectional"))
    )
    (net (code "13") (name "/GSM_STATUS") (class "Default")
      (node (ref "N1") (pin "10") (pinfunction "PA0/ADC0_10") (pintype "bidirectional"))
      (node (ref "U6") (pin "P$12") (pinfunction "B8_P$12") (pintype "bidirectional"))
    )
    (net (code "14") (name "/GSM_TXD") (class "Default")
      (node (ref "N1") (pin "17") (pinfunction "PD2/RXD1_17") (pintype "bidirectional"))
      (node (ref "U6") (pin "P$14") (pinfunction "B6_P$14") (pintype "bidirectional"))
    )
    (net (code "15") (name "/I2C_SCL") (class "Default")
      (node (ref "J3") (pin "CLK") (pinfunction "CLK_CLK") (pintype "bidirectional"))
      (node (ref "N1") (pin "23") (pinfunction "PC0/SCL_23") (pintype "bidirectional"))
      (node (ref "R10") (pin "1") (pinfunction "1_1") (pintype "bidirectional"))
      (node (ref "U12") (pin "32") (pinfunction "SCL_32") (pintype "bidirectional"))
      (node (ref "U3") (pin "19") (pinfunction "SCL_19") (pintype "bidirectional"))
      (node (ref "U4") (pin "19") (pinfunction "SCL_19") (pintype "bidirectional"))
      (node (ref "U5") (pin "19") (pinfunction "SCL_19") (pintype "bidirectional"))
    )
    (net (code "16") (name "/I2C_SDA") (class "Default")
      (node (ref "J3") (pin "DATA") (pinfunction "DATA_DATA") (pintype "bidirectional"))
      (node (ref "N1") (pin "24") (pinfunction "PC1/SDA_24") (pintype "bidirectional"))
      (node (ref "R20") (pin "1") (pinfunction "1_1") (pintype "bidirectional"))
      (node (ref "U12") (pin "31") (pinfunction "SDA_31") (pintype "bidirectional"))
      (node (ref "U3") (pin "20") (pinfunction "SDA_20") (pintype "bidirectional"))
      (node (ref "U4") (pin "20") (pinfunction "SDA_20") (pintype "bidirectional"))
      (node (ref "U5") (pin "20") (pinfunction "SDA_20") (pintype "bidirectional"))
    )
    (net (code "17") (name "/MICROSD_CS") (class "Default")
      (node (ref "J4") (pin "DAT3/CS") (pinfunction "DAT3/CS_DAT3/CS") (pintype "bidirectional"))
      (node (ref "N1") (pin "21") (pinfunction "PD6_21") (pintype "bidirectional"))
    )
    (net (code "18") (name "/OLED_RST") (class "Default")
      (node (ref "J3") (pin "RST") (pinfunction "RST_RST") (pintype "bidirectional"))
      (node (ref "N1") (pin "4") (pinfunction "PA6/ADC6_4") (pintype "bidirectional"))
    )
    (net (code "19") (name "/SPI_MISO") (class "Default")
      (node (ref "J4") (pin "DAT0/DO") (pinfunction "DAT0/DO_DAT0/DO") (pintype "bidirectional"))
      (node (ref "N1") (pin "32") (pinfunction "MISO_32") (pintype "bidirectional"))
    )
    (net (code "20") (name "/SPI_MOSI") (class "Default")
      (node (ref "J4") (pin "CMD/DI") (pinfunction "CMD/DI_CMD/DI") (pintype "bidirectional"))
      (node (ref "N1") (pin "31") (pinfunction "MOSI_31") (pintype "bidirectional"))
      (node (ref "U12") (pin "34") (pinfunction "SDI_34") (pintype "bidirectional"))
    )
    (net (code "21") (name "/SPI_SCK") (class "Default")
      (node (ref "J4") (pin "CLK/SCK") (pinfunction "CLK/SCK_CLK/SCK") (pintype "bidirectional"))
      (node (ref "N1") (pin "33") (pinfunction "SCK_33") (pintype "bidirectional"))
      (node (ref "U12") (pin "36") (pinfunction "SCKR_36") (pintype "bidirectional"))
    )
    (net (code "22") (name "/STA013_BIT_EN") (class "Default")
      (node (ref "N1") (pin "27") (pinfunction "PC4_27") (pintype "bidirectional"))
      (node (ref "U12") (pin "38") (pinfunction "BIT_EN_38") (pintype "bidirectional"))
    )
    (net (code "23") (name "/STA013_DREQ") (class "Default")
      (node (ref "N1") (pin "25") (pinfunction "PC2_25") (pintype "bidirectional"))
      (node (ref "U12") (pin "27") (pinfunction "OUT_CLK/DATA_REC_27") (pintype "bidirectional"))
    )
    (net (code "24") (name "/STA013_LRCKT") (class "Default")
      (node (ref "U12") (pin "2") (pinfunction "LRCKT_2") (pintype "bidirectional"))
      (node (ref "U13") (pin "P$3") (pinfunction "LRCK_P$3") (pintype "bidirectional"))
    )
    (net (code "25") (name "/STA013_OCLK") (class "Default")
      (node (ref "U12") (pin "3") (pinfunction "OCLK_3") (pintype "bidirectional"))
      (node (ref "U13") (pin "P$4") (pinfunction "MCLK_P$4") (pintype "bidirectional"))
    )
    (net (code "26") (name "/STA013_SCKT") (class "Default")
      (node (ref "U12") (pin "44") (pinfunction "SCKT_44") (pintype "bidirectional"))
      (node (ref "U13") (pin "P$2") (pinfunction "DEM/SCLK_P$2") (pintype "bidirectional"))
    )
    (net (code "27") (name "/STA013_SDO") (class "Default")
      (node (ref "U12") (pin "42") (pinfunction "SDO_42") (pintype "bidirectional"))
      (node (ref "U13") (pin "P$1") (pinfunction "SDATA_P$1") (pintype "bidirectional"))
    )
    (net (code "28") (name "/VBAT") (class "Default")
      (node (ref "BAT[+-]") (pin "1") (pinfunction "1_1") (pintype "bidirectional"))
      (node (ref "S1") (pin "2") (pinfunction "1_2") (pintype "bidirectional"))
    )
    (net (code "29") (name "/VIBRATOR_EN") (class "Default")
      (node (ref "N1") (pin "14") (pinfunction "PB3_14") (pintype "bidirectional"))
      (node (ref "R23") (pin "1") (pinfunction "1_1") (pintype "bidirectional"))
      (node (ref "U16") (pin "2") (pinfunction "A_2") (pintype "bidirectional"))
    )
    (net (code "30") (name "/~{STA013_RST}") (class "Default")
      (node (ref "N1") (pin "26") (pinfunction "PC3_26") (pintype "bidirectional"))
      (node (ref "R14") (pin "1") (pinfunction "1_1") (pintype "bidirectional"))
      (node (ref "U12") (pin "25") (pinfunction "~{RESET}_25") (pintype "bidirectional"))
    )
    (net (code "31") (name "GND") (class "Default")
      (node (ref "B1") (pin "2") (pinfunction "2_2") (pintype "bidirectional"))
      (node (ref "B10") (pin "2") (pinfunction "2_2") (pintype "bidirectional"))
      (node (ref "B11") (pin "2") (pinfunction "2_2") (pintype "bidirectional"))
      (node (ref "B12") (pin "2") (pinfunction "2_2") (pintype "bidirectional"))
      (node (ref "B13") (pin "5") (pinfunction "COMMON_5") (pintype "bidirectional"))
      (node (ref "B13") (pin "GND1") (pinfunction "GND1_GND1") (pintype "bidirectional"))
      (node (ref "B13") (pin "GND2") (pinfunction "GND2_GND2") (pintype "bidirectional"))
      (node (ref "B14") (pin "1") (pinfunction "1_1") (pintype "bidirectional"))
      (node (ref "B15") (pin "2") (pinfunction "2_2") (pintype "bidirectional"))
      (node (ref "B16") (pin "1") (pinfunction "1_1") (pintype "bidirectional"))
      (node (ref "B17") (pin "2") (pinfunction "2_2") (pintype "bidirectional"))
      (node (ref "B2") (pin "2") (pinfunction "2_2") (pintype "bidirectional"))
      (node (ref "B3") (pin "2") (pinfunction "2_2") (pintype "bidirectional"))
      (node (ref "B4") (pin "2") (pinfunction "2_2") (pintype "bidirectional"))
      (node (ref "B5") (pin "2") (pinfunction "2_2") (pintype "bidirectional"))
      (node (ref "B6") (pin "2") (pinfunction "2_2") (pintype "bidirectional"))
      (node (ref "B7") (pin "2") (pinfunction "2_2") (pintype "bidirectional"))
      (node (ref "B8") (pin "2") (pinfunction "2_2") (pintype "bidirectional"))
      (node (ref "B9") (pin "2") (pinfunction "2_2") (pintype "bidirectional"))
      (node (ref "BAT[+-]") (pin "2") (pinfunction "2_2") (pintype "bidirectional"))
      (node (ref "C1") (pin "1") (pinfunction "1_1") (pintype "bidirectional"))
      (node (ref "C10") (pin "2") (pinfunction "2_2") (pintype "bidirectional"))
      (node (ref "C13") (pin "1") (pinfunction "1_1") (pintype "bidirectional"))
      (node (ref "C14") (pin "1") (pinfunction "1_1") (pintype "bidirectional"))
      (node (ref "C15") (pin "1") (pinfunction "1_1") (pintype "bidirectional"))
      (node (ref "C16") (pin "1") (pinfunction "1_1") (pintype "bidirectional"))
      (node (ref "C19") (pin "1") (pinfunction "1_1") (pintype "bidirectional"))
      (node (ref "C2") (pin "1") (pinfunction "1_1") (pintype "bidirectional"))
      (node (ref "C20") (pin "1") (pinfunction "1_1") (pintype "bidirectional"))
      (node (ref "C21") (pin "1") (pinfunction "1_1") (pintype "bidirectional"))
      (node (ref "C22") (pin "1") (pinfunction "1_1") (pintype "bidirectional"))
      (node (ref "C23") (pin "1") (pinfunction "1_1") (pintype "bidirectional"))
      (node (ref "C24") (pin "1") (pinfunction "1_1") (pintype "bidirectional"))
      (node (ref "C25") (pin "2") (pinfunction "2_2") (pintype "bidirectional"))
      (node (ref "C26") (pin "1") (pinfunction "1_1") (pintype "bidirectional"))
      (node (ref "C27") (pin "1") (pinfunction "1_1") (pintype "bidirectional"))
      (node (ref "C28") (pin "1") (pinfunction "1_1") (pintype "bidirectional"))
      (node (ref "C29") (pin "2") (pinfunction "2_2") (pintype "bidirectional"))
      (node (ref "C3") (pin "2") (pinfunction "2_2") (pintype "bidirectional"))
      (node (ref "C30") (pin "2") (pinfunction "2_2") (pintype "bidirectional"))
      (node (ref "C31") (pin "2") (pinfunction "2_2") (pintype "bidirectional"))
      (node (ref "C32") (pin "2") (pinfunction "2_2") (pintype "bidirectional"))
      (node (ref "C33") (pin "1") (pinfunction "1_1") (pintype "bidirectional"))
      (node (ref "C34") (pin "1") (pinfunction "1_1") (pintype "bidirectional"))
      (node (ref "C35") (pin "1") (pinfunction "1_1") (pintype "bidirectional"))
      (node (ref "C36") (pin "1") (pinfunction "1_1") (pintype "bidirectional"))
      (node (ref "C37") (pin "1") (pinfunction "1_1") (pintype "bidirectional"))
      (node (ref "C38") (pin "1") (pinfunction "1_1") (pintype "bidirectional"))
      (node (ref "C4") (pin "2") (pinfunction "2_2") (pintype "bidirectional"))
      (node (ref "C40") (pin "1") (pinfunction "1_1") (pintype "bidirectional"))
      (node (ref "C41") (pin "1") (pinfunction "1_1") (pintype "bidirectional"))
      (node (ref "C42") (pin "1") (pinfunction "1_1") (pintype "bidirectional"))
      (node (ref "C45") (pin "2") (pinfunction "2_2") (pintype "bidirectional"))
      (node (ref "C46") (pin "2") (pinfunction "2_2") (pintype "bidirectional"))
      (node (ref "C47") (pin "1") (pinfunction "1_1") (pintype "bidirectional"))
      (node (ref "C48") (pin "1") (pinfunction "1_1") (pintype "bidirectional"))
      (node (ref "C5") (pin "2") (pinfunction "2_2") (pintype "bidirectional"))
      (node (ref "C51") (pin "1") (pinfunction "1_1") (pintype "bidirectional"))
      (node (ref "C54") (pin "1") (pinfunction "1_1") (pintype "bidirectional"))
      (node (ref "C55") (pin "1") (pinfunction "1_1") (pintype "bidirectional"))
      (node (ref "C56") (pin "2") (pinfunction "2_2") (pintype "bidirectional"))
      (node (ref "C6") (pin "2") (pinfunction "2_2") (pintype "bidirectional"))
      (node (ref "C7") (pin "1") (pinfunction "1_1") (pintype "bidirectional"))
      (node (ref "C8") (pin "1") (pinfunction "1_1") (pintype "bidirectional"))
      (node (ref "C9") (pin "1") (pinfunction "1_1") (pintype "bidirectional"))
      (node (ref "D1") (pin "2") (pinfunction "2_2") (pintype "bidirectional"))
      (node (ref "D2") (pin "2") (pinfunction "2_2") (pintype "bidirectional"))
      (node (ref "J3") (pin "GND") (pinfunction "GND_GND") (pintype "bidirectional"))
      (node (ref "J4") (pin "GND1") (pinfunction "GND_1_GND1") (pintype "bidirectional"))
      (node (ref "J4") (pin "GND2") (pinfunction "GND_2_GND2") (pintype "bidirectional"))
      (node (ref "J4") (pin "GND3") (pinfunction "GND_3_GND3") (pintype "bidirectional"))
      (node (ref "J4") (pin "GND4") (pinfunction "GND_4_GND4") (pintype "bidirectional"))
      (node (ref "J4") (pin "VSS") (pinfunction "GND_VSS") (pintype "bidirectional"))
      (node (ref "J5") (pin "1") (pinfunction "SLEEVE_1") (pintype "bidirectional"))
      (node (ref "J6") (pin "P$1") (pinfunction "GND_P$1") (pintype "bidirectional"))
      (node (ref "J6") (pin "P$2") (pinfunction "GND_P$2") (pintype "bidirectional"))
      (node (ref "M1") (pin "1") (pinfunction "-_1") (pintype "bidirectional"))
      (node (ref "N1") (pin "1") (pinfunction "GND_1") (pintype "bidirectional"))
      (node (ref "N1") (pin "15") (pinfunction "GND_15") (pintype "bidirectional"))
      (node (ref "N1") (pin "35") (pinfunction "GND_35") (pintype "bidirectional"))
      (node (ref "R1") (pin "1") (pinfunction "1_1") (pintype "bidirectional"))
      (node (ref "R12") (pin "2") (pinfunction "2_2") (pintype "bidirectional"))
      (node (ref "R18") (pin "2") (pinfunction "2_2") (pintype "bidirectional"))
      (node (ref "R19") (pin "1") (pinfunction "1_1") (pintype "bidirectional"))
      (node (ref "R2") (pin "1") (pinfunction "1_1") (pintype "bidirectional"))
      (node (ref "R23") (pin "2") (pinfunction "2_2") (pintype "bidirectional"))
      (node (ref "R3") (pin "2") (pinfunction "2_2") (pintype "bidirectional"))
      (node (ref "R4") (pin "2") (pinfunction "2_2") (pintype "bidirectional"))
      (node (ref "R6") (pin "2") (pinfunction "2_2") (pintype "bidirectional"))
      (node (ref "U1") (pin "P$17") (pinfunction "GND_P$17") (pintype "bidirectional"))
      (node (ref "U1") (pin "P$18") (pinfunction "GND_P$18") (pintype "bidirectional"))
      (node (ref "U1") (pin "P$2") (pinfunction "GND_P$2") (pintype "bidirectional"))
      (node (ref "U1") (pin "P$29") (pinfunction "GND_P$29") (pintype "bidirectional"))
      (node (ref "U1") (pin "P$39") (pinfunction "GND_P$39") (pintype "bidirectional"))
      (node (ref "U1") (pin "P$45") (pinfunction "GND_P$45") (pintype "bidirectional"))
      (node (ref "U1") (pin "P$46") (pinfunction "GND_P$46") (pintype "bidirectional"))
      (node (ref "U1") (pin "P$54") (pinfunction "GND_P$54") (pintype "bidirectional"))
      (node (ref "U1") (pin "P$58") (pinfunction "GND_P$58") (pintype "bidirectional"))
      (node (ref "U1") (pin "P$59") (pinfunction "GND_P$59") (pintype "bidirectional"))
      (node (ref "U1") (pin "P$61") (pinfunction "GND_P$61") (pintype "bidirectional"))
      (node (ref "U1") (pin "P$62") (pinfunction "GND_P$62") (pintype "bidirectional"))
      (node (ref "U1") (pin "P$63") (pinfunction "GND_P$63") (pintype "bidirectional"))
      (node (ref "U1") (pin "P$64") (pinfunction "GND_P$64") (pintype "bidirectional"))
      (node (ref "U1") (pin "P$65") (pinfunction "GND_P$65") (pintype "bidirectional"))
      (node (ref "U10") (pin "2") (pinfunction "GND_2") (pintype "bidirectional"))
      (node (ref "U11") (pin "6") (pinfunction "PGND_6") (pintype "bidirectional"))
      (node (ref "U11") (pin "7") (pinfunction "SGND_7") (pintype "bidirectional"))
      (node (ref "U12") (pin "19") (pinfunction "VSS_4_19") (pintype "bidirectional"))
      (node (ref "U12") (pin "24") (pinfunction "SCANEN_24") (pintype "bidirectional"))
      (node (ref "U12") (pin "26") (pinfunction "VSS_5_26") (pintype "bidirectional"))
      (node (ref "U12") (pin "30") (pinfunction "VSS_1_30") (pintype "bidirectional"))
      (node (ref "U12") (pin "5") (pinfunction "VSS_2_5") (pintype "bidirectional"))
      (node (ref "U12") (pin "7") (pinfunction "VSS_3_7") (pintype "bidirectional"))
      (node (ref "U13") (pin "P$6") (pinfunction "AGND_P$6") (pintype "bidirectional"))
      (node (ref "U14") (pin "5") (pinfunction "GND_5") (pintype "bidirectional"))
      (node (ref "U15") (pin "2") (pinfunction "GND_2") (pintype "bidirectional"))
      (node (ref "U16") (pin "1") (pinfunction "~{OE}_1") (pintype "bidirectional"))
      (node (ref "U16") (pin "3") (pinfunction "GND_3") (pintype "bidirectional"))
      (node (ref "U2") (pin "P$3") (pinfunction "GND_P$3") (pintype "bidirectional"))
      (node (ref "U2") (pin "P$6") (pinfunction "GND_P$6") (pintype "bidirectional"))
      (node (ref "U3") (pin "17") (pinfunction "GND_17") (pintype "bidirectional"))
      (node (ref "U3") (pin "2") (pinfunction "A1_2") (pintype "bidirectional"))
      (node (ref "U3") (pin "3") (pinfunction "A0_3") (pintype "bidirectional"))
      (node (ref "U3") (pin "PAD") (pinfunction "PAD_PAD") (pintype "bidirectional"))
      (node (ref "U4") (pin "17") (pinfunction "GND_17") (pintype "bidirectional"))
      (node (ref "U4") (pin "2") (pinfunction "A1_2") (pintype "bidirectional"))
      (node (ref "U4") (pin "PAD") (pinfunction "PAD_PAD") (pintype "bidirectional"))
      (node (ref "U5") (pin "17") (pinfunction "GND_17") (pintype "bidirectional"))
      (node (ref "U5") (pin "3") (pinfunction "A0_3") (pintype "bidirectional"))
      (node (ref "U5") (pin "PAD") (pinfunction "PAD_PAD") (pintype "bidirectional"))
      (node (ref "U6") (pin "P$11") (pinfunction "GND_P$11") (pintype "bidirectional"))
      (node (ref "U7") (pin "1") (pinfunction "~{OE}_1") (pintype "bidirectional"))
      (node (ref "U7") (pin "3") (pinfunction "GND_3") (pintype "bidirectional"))
      (node (ref "U8") (pin "C5") (pinfunction "GND_C5") (pintype "bidirectional"))
      (node (ref "U8") (pin "GND@L") (pinfunction "GND_GND@L") (pintype "bidirectional"))
      (node (ref "U8") (pin "GND@R") (pinfunction "GND_GND@R") (pintype "bidirectional"))
      (node (ref "U9") (pin "P$2") (pinfunction "COMMON_P$2") (pintype "bidirectional"))
      (node (ref "X2") (pin "2") (pinfunction "GND0_2") (pintype "bidirectional"))
      (node (ref "X2") (pin "4") (pinfunction "GND1_4") (pintype "bidirectional"))
    )
    (net (code "32") (name "Net-(B13-A)") (class "Default")
      (node (ref "B13") (pin "1") (pinfunction "A_1") (pintype "bidirectional"))
      (node (ref "U3") (pin "12") (pinfunction "GP3_12") (pintype "bidirectional"))
    )
    (net (code "33") (name "Net-(B13-B)") (class "Default")
      (node (ref "B13") (pin "4") (pinfunction "B_4") (pintype "bidirectional"))
      (node (ref "U3") (pin "10") (pinfunction "GP1_10") (pintype "bidirectional"))
    )
    (net (code "34") (name "Net-(B13-C)") (class "Default")
      (node (ref "B13") (pin "3") (pinfunction "C_3") (pintype "bidirectional"))
      (node (ref "U3") (pin "14") (pinfunction "GP5_14") (pintype "bidirectional"))
    )
    (net (code "35") (name "Net-(B13-CENTER)") (class "Default")
      (node (ref "B13") (pin "2") (pinfunction "CENTER_2") (pintype "bidirectional"))
      (node (ref "U3") (pin "13") (pinfunction "GP4_13") (pintype "bidirectional"))
    )
    (net (code "36") (name "Net-(B13-D)") (class "Default")
      (node (ref "B13") (pin "6") (pinfunction "D_6") (pintype "bidirectional"))
      (node (ref "U3") (pin "11") (pinfunction "GP2_11") (pintype "bidirectional"))
    )
    (net (code "37") (name "Net-(C41-Pad2)") (class "Default")
      (node (ref "C41") (pin "2") (pinfunction "2_2") (pintype "bidirectional"))
      (node (ref "R15") (pin "2") (pinfunction "2_2") (pintype "bidirectional"))
    )
    (net (code "38") (name "Net-(C43-Pad1)") (class "Default")
      (node (ref "C43") (pin "1") (pinfunction "1_1") (pintype "bidirectional"))
      (node (ref "R17") (pin "1") (pinfunction "1_1") (pintype "bidirectional"))
    )
    (net (code "39") (name "Net-(C44-Pad1)") (class "Default")
      (node (ref "C44") (pin "1") (pinfunction "1_1") (pintype "bidirectional"))
      (node (ref "R16") (pin "1") (pinfunction "1_1") (pintype "bidirectional"))
    )
    (net (code "40") (name "Net-(D1-Pad1)") (class "Default")
      (node (ref "D1") (pin "1") (pinfunction "1_1") (pintype "bidirectional"))
      (node (ref "R21") (pin "2") (pinfunction "2_2") (pintype "bidirectional"))
    )
    (net (code "41") (name "Net-(D2-Pad1)") (class "Default")
      (node (ref "D2") (pin "1") (pinfunction "1_1") (pintype "bidirectional"))
      (node (ref "R24") (pin "2") (pinfunction "2_2") (pintype "bidirectional"))
    )
    (net (code "42") (name "Net-(J5-RING)") (class "Default")
      (node (ref "C50") (pin "1") (pinfunction "1_1") (pintype "bidirectional"))
      (node (ref "J5") (pin "3") (pinfunction "RING_3") (pintype "bidirectional"))
    )
    (net (code "43") (name "Net-(J5-TIP)") (class "Default")
      (node (ref "C49") (pin "1") (pinfunction "1_1") (pintype "bidirectional"))
      (node (ref "J5") (pin "2") (pinfunction "TIP_2") (pintype "bidirectional"))
    )
    (net (code "44") (name "Net-(J6-SIG)") (class "Default")
      (node (ref "J6") (pin "P$3") (pinfunction "SIG_P$3") (pintype "bidirectional"))
      (node (ref "U1") (pin "P$60") (pinfunction "RF_ANT_P$60") (pintype "bidirectional"))
    )
    (net (code "45") (name "Net-(M1-+)") (class "Default")
      (node (ref "C55") (pin "2") (pinfunction "2_2") (pintype "bidirectional"))
      (node (ref "M1") (pin "2") (pinfunction "+_2") (pintype "bidirectional"))
      (node (ref "U15") (pin "5") (pinfunction "VOUT_5") (pintype "bidirectional"))
    )
    (net (code "46") (name "Net-(N1-PD4)") (class "Default")
      (node (ref "N1") (pin "19") (pinfunction "PD4_19") (pintype "bidirectional"))
      (node (ref "R24") (pin "1") (pinfunction "1_1") (pintype "bidirectional"))
    )
    (net (code "47") (name "Net-(N1-PD5)") (class "Default")
      (node (ref "N1") (pin "20") (pinfunction "PD5_20") (pintype "bidirectional"))
      (node (ref "R21") (pin "1") (pinfunction "1_1") (pintype "bidirectional"))
    )
    (net (code "48") (name "Net-(S1-2)") (class "Default")
      (node (ref "C25") (pin "1") (pinfunction "1_1") (pintype "bidirectional"))
      (node (ref "L1") (pin "1") (pinfunction "1_1") (pintype "bidirectional"))
      (node (ref "S1") (pin "3") (pinfunction "2_3") (pintype "bidirectional"))
      (node (ref "U11") (pin "1") (pinfunction "EN_1") (pintype "bidirectional"))
      (node (ref "U11") (pin "8") (pinfunction "VIN_8") (pintype "bidirectional"))
    )
    (net (code "49") (name "Net-(U1-MIC_N)") (class "Default")
      (node (ref "C17") (pin "1") (pinfunction "1_1") (pintype "bidirectional"))
      (node (ref "C18") (pin "1") (pinfunction "1_1") (pintype "bidirectional"))
      (node (ref "C19") (pin "2") (pinfunction "2_2") (pintype "bidirectional"))
      (node (ref "C22") (pin "2") (pinfunction "2_2") (pintype "bidirectional"))
      (node (ref "J2") (pin "-") (pinfunction "-_-") (pintype "bidirectional"))
      (node (ref "U1") (pin "P$20") (pinfunction "MIC_N_P$20") (pintype "bidirectional"))
    )
    (net (code "50") (name "Net-(U1-MIC_P)") (class "Default")
      (node (ref "C17") (pin "2") (pinfunction "2_2") (pintype "bidirectional"))
      (node (ref "C18") (pin "2") (pinfunction "2_2") (pintype "bidirectional"))
      (node (ref "C20") (pin "2") (pinfunction "2_2") (pintype "bidirectional"))
      (node (ref "C21") (pin "2") (pinfunction "2_2") (pintype "bidirectional"))
      (node (ref "J2") (pin "+") (pinfunction "+_+") (pintype "bidirectional"))
      (node (ref "U1") (pin "P$19") (pinfunction "MIC_P_P$19") (pintype "bidirectional"))
    )
    (net (code "51") (name "Net-(U1-RI)") (class "Default")
      (node (ref "U1") (pin "P$4") (pinfunction "RI_P$4") (pintype "bidirectional"))
      (node (ref "U6") (pin "P$8") (pinfunction "A7_P$8") (pintype "bidirectional"))
    )
    (net (code "52") (name "Net-(U1-RXD)") (class "Default")
      (node (ref "U1") (pin "P$10") (pinfunction "RXD_P$10") (pintype "bidirectional"))
      (node (ref "U6") (pin "P$6") (pinfunction "A5_P$6") (pintype "bidirectional"))
    )
    (net (code "53") (name "Net-(U1-SPK_N)") (class "Default")
      (node (ref "C11") (pin "2") (pinfunction "2_2") (pintype "bidirectional"))
      (node (ref "C12") (pin "2") (pinfunction "2_2") (pintype "bidirectional"))
      (node (ref "C14") (pin "2") (pinfunction "2_2") (pintype "bidirectional"))
      (node (ref "C15") (pin "2") (pinfunction "2_2") (pintype "bidirectional"))
      (node (ref "J1") (pin "-") (pinfunction "-_-") (pintype "bidirectional"))
      (node (ref "U1") (pin "P$22") (pinfunction "SPK_N_P$22") (pintype "bidirectional"))
    )
    (net (code "54") (name "Net-(U1-SPK_P)") (class "Default")
      (node (ref "C11") (pin "1") (pinfunction "1_1") (pintype "bidirectional"))
      (node (ref "C12") (pin "1") (pinfunction "1_1") (pintype "bidirectional"))
      (node (ref "C13") (pin "2") (pinfunction "2_2") (pintype "bidirectional"))
      (node (ref "C16") (pin "2") (pinfunction "2_2") (pintype "bidirectional"))
      (node (ref "J1") (pin "+") (pinfunction "+_+") (pintype "bidirectional"))
      (node (ref "U1") (pin "P$21") (pinfunction "SPK_P_P$21") (pintype "bidirectional"))
    )
    (net (code "55") (name "Net-(U1-STATUS)") (class "Default")
      (node (ref "U1") (pin "P$66") (pinfunction "STATUS_P$66") (pintype "bidirectional"))
      (node (ref "U6") (pin "P$9") (pinfunction "A8_P$9") (pintype "bidirectional"))
    )
    (net (code "56") (name "Net-(U1-TXD)") (class "Default")
      (node (ref "U1") (pin "P$9") (pinfunction "TXD_P$9") (pintype "bidirectional"))
      (node (ref "U6") (pin "P$7") (pinfunction "A6_P$7") (pintype "bidirectional"))
    )
    (net (code "57") (name "Net-(U1-USIM_CLK)") (class "Default")
      (node (ref "C8") (pin "2") (pinfunction "2_2") (pintype "bidirectional"))
      (node (ref "R8") (pin "2") (pinfunction "2_2") (pintype "bidirectional"))
      (node (ref "U1") (pin "P$32") (pinfunction "USIM_CLK_P$32") (pintype "bidirectional"))
    )
    (net (code "58") (name "Net-(U1-USIM_DATA)") (class "Default")
      (node (ref "C7") (pin "2") (pinfunction "2_2") (pintype "bidirectional"))
      (node (ref "R9") (pin "2") (pinfunction "2_2") (pintype "bidirectional"))
      (node (ref "U1") (pin "P$31") (pinfunction "USIM_DATA_P$31") (pintype "bidirectional"))
    )
    (net (code "59") (name "Net-(U1-USIM_RST)") (class "Default")
      (node (ref "C9") (pin "2") (pinfunction "2_2") (pintype "bidirectional"))
      (node (ref "R7") (pin "2") (pinfunction "2_2") (pintype "bidirectional"))
      (node (ref "U1") (pin "P$33") (pinfunction "USIM_RST_P$33") (pintype "bidirectional"))
    )
    (net (code "60") (name "Net-(U1-USIM_VDD)") (class "Default")
      (node (ref "C10") (pin "1") (pinfunction "1_1") (pintype "bidirectional"))
      (node (ref "U1") (pin "P$30") (pinfunction "USIM_VDD_P$30") (pintype "bidirectional"))
      (node (ref "U8") (pin "C1") (pinfunction "VCC_C1") (pintype "bidirectional"))
      (node (ref "U9") (pin "P$6") (pinfunction "X5_P$6") (pintype "bidirectional"))
    )
    (net (code "61") (name "Net-(U1-VDD_EXT)") (class "Default")
      (node (ref "C1") (pin "2") (pinfunction "2_2") (pintype "bidirectional"))
      (node (ref "U1") (pin "P$15") (pinfunction "VDD_EXT_P$15") (pintype "bidirectional"))
      (node (ref "U6") (pin "P$10") (pinfunction "OE_P$10") (pintype "bidirectional"))
      (node (ref "U6") (pin "P$2") (pinfunction "VCCA_P$2") (pintype "bidirectional"))
    )
    (net (code "62") (name "Net-(U2-ADJ)") (class "Default")
      (node (ref "R4") (pin "1") (pinfunction "1_1") (pintype "bidirectional"))
      (node (ref "R5") (pin "2") (pinfunction "2_2") (pintype "bidirectional"))
      (node (ref "U2") (pin "P$5") (pinfunction "ADJ_P$5") (pintype "bidirectional"))
    )
    (net (code "63") (name "Net-(U2-EN)") (class "Default")
      (node (ref "U2") (pin "P$1") (pinfunction "EN_P$1") (pintype "bidirectional"))
      (node (ref "U7") (pin "4") (pinfunction "Y_4") (pintype "bidirectional"))
    )
    (net (code "64") (name "Net-(U3-GP0)") (class "Default")
      (node (ref "B16") (pin "2") (pinfunction "2_2") (pintype "bidirectional"))
      (node (ref "U3") (pin "9") (pinfunction "GP0_9") (pintype "bidirectional"))
    )
    (net (code "65") (name "Net-(U3-GP6)") (class "Default")
      (node (ref "B14") (pin "2") (pinfunction "2_2") (pintype "bidirectional"))
      (node (ref "U3") (pin "15") (pinfunction "GP6_15") (pintype "bidirectional"))
    )
    (net (code "66") (name "Net-(U3-GP7)") (class "Default")
      (node (ref "B17") (pin "1") (pinfunction "1_1") (pintype "bidirectional"))
      (node (ref "U3") (pin "16") (pinfunction "GP7_16") (pintype "bidirectional"))
    )
    (net (code "67") (name "Net-(U4-GP0)") (class "Default")
      (node (ref "B15") (pin "1") (pinfunction "1_1") (pintype "bidirectional"))
      (node (ref "U4") (pin "9") (pinfunction "GP0_9") (pintype "bidirectional"))
    )
    (net (code "68") (name "Net-(U4-GP1)") (class "Default")
      (node (ref "B9") (pin "1") (pinfunction "1_1") (pintype "bidirectional"))
      (node (ref "U4") (pin "10") (pinfunction "GP1_10") (pintype "bidirectional"))
    )
    (net (code "69") (name "Net-(U4-GP2)") (class "Default")
      (node (ref "B5") (pin "1") (pinfunction "1_1") (pintype "bidirectional"))
      (node (ref "U4") (pin "11") (pinfunction "GP2_11") (pintype "bidirectional"))
    )
    (net (code "70") (name "Net-(U4-GP3)") (class "Default")
      (node (ref "B1") (pin "1") (pinfunction "1_1") (pintype "bidirectional"))
      (node (ref "U4") (pin "12") (pinfunction "GP3_12") (pintype "bidirectional"))
    )
    (net (code "71") (name "Net-(U4-GP4)") (class "Default")
      (node (ref "B10") (pin "1") (pinfunction "1_1") (pintype "bidirectional"))
      (node (ref "U4") (pin "13") (pinfunction "GP4_13") (pintype "bidirectional"))
    )
    (net (code "72") (name "Net-(U4-GP5)") (class "Default")
      (node (ref "B6") (pin "1") (pinfunction "1_1") (pintype "bidirectional"))
      (node (ref "U4") (pin "14") (pinfunction "GP5_14") (pintype "bidirectional"))
    )
    (net (code "73") (name "Net-(U4-GP6)") (class "Default")
      (node (ref "B2") (pin "1") (pinfunction "1_1") (pintype "bidirectional"))
      (node (ref "U4") (pin "15") (pinfunction "GP6_15") (pintype "bidirectional"))
    )
    (net (code "74") (name "Net-(U4-GP7)") (class "Default")
      (node (ref "B11") (pin "1") (pinfunction "1_1") (pintype "bidirectional"))
      (node (ref "U4") (pin "16") (pinfunction "GP7_16") (pintype "bidirectional"))
    )
    (net (code "75") (name "Net-(U5-GP0)") (class "Default")
      (node (ref "B3") (pin "1") (pinfunction "1_1") (pintype "bidirectional"))
      (node (ref "U5") (pin "9") (pinfunction "GP0_9") (pintype "bidirectional"))
    )
    (net (code "76") (name "Net-(U5-GP1)") (class "Default")
      (node (ref "B4") (pin "1") (pinfunction "1_1") (pintype "bidirectional"))
      (node (ref "U5") (pin "10") (pinfunction "GP1_10") (pintype "bidirectional"))
    )
    (net (code "77") (name "Net-(U5-GP2)") (class "Default")
      (node (ref "B7") (pin "1") (pinfunction "1_1") (pintype "bidirectional"))
      (node (ref "U5") (pin "11") (pinfunction "GP2_11") (pintype "bidirectional"))
    )
    (net (code "78") (name "Net-(U5-GP3)") (class "Default")
      (node (ref "B8") (pin "1") (pinfunction "1_1") (pintype "bidirectional"))
      (node (ref "U5") (pin "12") (pinfunction "GP3_12") (pintype "bidirectional"))
    )
    (net (code "79") (name "Net-(U5-GP4)") (class "Default")
      (node (ref "B12") (pin "1") (pinfunction "1_1") (pintype "bidirectional"))
      (node (ref "U5") (pin "13") (pinfunction "GP4_13") (pintype "bidirectional"))
    )
    (net (code "80") (name "Net-(U6-A1)") (class "Default")
      (node (ref "R2") (pin "2") (pinfunction "2_2") (pintype "bidirectional"))
      (node (ref "U6") (pin "P$1") (pinfunction "A1_P$1") (pintype "bidirectional"))
      (node (ref "U6") (pin "P$3") (pinfunction "A2_P$3") (pintype "bidirectional"))
      (node (ref "U6") (pin "P$4") (pinfunction "A3_P$4") (pintype "bidirectional"))
      (node (ref "U6") (pin "P$5") (pinfunction "A4_P$5") (pintype "bidirectional"))
    )
    (net (code "81") (name "Net-(U6-B1)") (class "Default")
      (node (ref "R1") (pin "2") (pinfunction "2_2") (pintype "bidirectional"))
      (node (ref "U6") (pin "P$16") (pinfunction "B4_P$16") (pintype "bidirectional"))
      (node (ref "U6") (pin "P$17") (pinfunction "B3_P$17") (pintype "bidirectional"))
      (node (ref "U6") (pin "P$18") (pinfunction "B2_P$18") (pintype "bidirectional"))
      (node (ref "U6") (pin "P$20") (pinfunction "B1_P$20") (pintype "bidirectional"))
    )
    (net (code "82") (name "Net-(U8-CLK)") (class "Default")
      (node (ref "R8") (pin "1") (pinfunction "1_1") (pintype "bidirectional"))
      (node (ref "U8") (pin "C3") (pinfunction "CLK_C3") (pintype "bidirectional"))
      (node (ref "U9") (pin "P$4") (pinfunction "X3_P$4") (pintype "bidirectional"))
    )
    (net (code "83") (name "Net-(U8-IO)") (class "Default")
      (node (ref "R9") (pin "1") (pinfunction "1_1") (pintype "bidirectional"))
      (node (ref "U8") (pin "C7") (pinfunction "IO_C7") (pintype "bidirectional"))
      (node (ref "U9") (pin "P$5") (pinfunction "X4_P$5") (pintype "bidirectional"))
    )
    (net (code "84") (name "Net-(U8-RST)") (class "Default")
      (node (ref "R7") (pin "1") (pinfunction "1_1") (pintype "bidirectional"))
      (node (ref "U8") (pin "C2") (pinfunction "RST_C2") (pintype "bidirectional"))
      (node (ref "U9") (pin "P$3") (pinfunction "X2_P$3") (pintype "bidirectional"))
    )
    (net (code "85") (name "Net-(U11-SW)") (class "Default")
      (node (ref "L1") (pin "2") (pinfunction "2_2") (pintype "bidirectional"))
      (node (ref "U11") (pin "5") (pinfunction "SW_5") (pintype "bidirectional"))
    )
    (net (code "86") (name "Net-(U12-FILT)") (class "Default")
      (node (ref "C40") (pin "2") (pinfunction "2_2") (pintype "bidirectional"))
      (node (ref "R15") (pin "1") (pinfunction "1_1") (pintype "bidirectional"))
      (node (ref "U12") (pin "12") (pinfunction "FILT_12") (pintype "bidirectional"))
    )
    (net (code "87") (name "Net-(U12-PVDD)") (class "Default")
      (node (ref "C39") (pin "1") (pinfunction "1_1") (pintype "bidirectional"))
      (node (ref "R13") (pin "2") (pinfunction "2_2") (pintype "bidirectional"))
      (node (ref "U12") (pin "10") (pinfunction "PVDD_10") (pintype "bidirectional"))
    )
    (net (code "88") (name "Net-(U12-PVSS)") (class "Default")
      (node (ref "C39") (pin "2") (pinfunction "2_2") (pintype "bidirectional"))
      (node (ref "R12") (pin "1") (pinfunction "1_1") (pintype "bidirectional"))
      (node (ref "U12") (pin "11") (pinfunction "PVSS_11") (pintype "bidirectional"))
    )
    (net (code "89") (name "Net-(U12-XTI)") (class "Default")
      (node (ref "C34") (pin "2") (pinfunction "2_2") (pintype "bidirectional"))
      (node (ref "R11") (pin "1") (pinfunction "1_1") (pintype "bidirectional"))
      (node (ref "U12") (pin "15") (pinfunction "XTI_15") (pintype "bidirectional"))
      (node (ref "X2") (pin "1") (pinfunction "1_1") (pintype "bidirectional"))
    )
    (net (code "90") (name "Net-(U12-XTO)") (class "Default")
      (node (ref "C33") (pin "2") (pinfunction "2_2") (pintype "bidirectional"))
      (node (ref "R11") (pin "2") (pinfunction "2_2") (pintype "bidirectional"))
      (node (ref "U12") (pin "13") (pinfunction "XTO_13") (pintype "bidirectional"))
      (node (ref "X2") (pin "3") (pinfunction "2_3") (pintype "bidirectional"))
    )
    (net (code "91") (name "Net-(U13-AOUTL)") (class "Default")
      (node (ref "C43") (pin "2") (pinfunction "2_2") (pintype "bidirectional"))
      (node (ref "R18") (pin "1") (pinfunction "1_1") (pintype "bidirectional"))
      (node (ref "U13") (pin "P$8") (pinfunction "AOUTL_P$8") (pintype "bidirectional"))
    )
    (net (code "92") (name "Net-(U13-AOUTR)") (class "Default")
      (node (ref "C44") (pin "2") (pinfunction "2_2") (pintype "bidirectional"))
      (node (ref "R19") (pin "2") (pinfunction "2_2") (pintype "bidirectional"))
      (node (ref "U13") (pin "P$5") (pinfunction "AOUTR_P$5") (pintype "bidirectional"))
    )
    (net (code "93") (name "Net-(U14-BYPASS)") (class "Default")
      (node (ref "C51") (pin "2") (pinfunction "2_2") (pintype "bidirectional"))
      (node (ref "U14") (pin "3") (pinfunction "BYPASS_3") (pintype "bidirectional"))
    )
    (net (code "94") (name "Net-(U14-VIN1)") (class "Default")
      (node (ref "C52") (pin "2") (pinfunction "2_2") (pintype "bidirectional"))
      (node (ref "U14") (pin "2") (pinfunction "VIN1_2") (pintype "bidirectional"))
    )
    (net (code "95") (name "Net-(U14-VIN2)") (class "Default")
      (node (ref "C53") (pin "2") (pinfunction "2_2") (pintype "bidirectional"))
      (node (ref "U14") (pin "8") (pinfunction "VIN2_8") (pintype "bidirectional"))
    )
    (net (code "96") (name "Net-(U14-VOUT1)") (class "Default")
      (node (ref "C49") (pin "2") (pinfunction "2_2") (pintype "bidirectional"))
      (node (ref "U14") (pin "1") (pinfunction "VOUT1_1") (pintype "bidirectional"))
    )
    (net (code "97") (name "Net-(U14-VOUT2)") (class "Default")
      (node (ref "C50") (pin "2") (pinfunction "2_2") (pintype "bidirectional"))
      (node (ref "U14") (pin "9") (pinfunction "VOUT2_9") (pintype "bidirectional"))
    )
    (net (code "98") (name "Net-(U15-EN)") (class "Default")
      (node (ref "U15") (pin "3") (pinfunction "EN_3") (pintype "bidirectional"))
      (node (ref "U16") (pin "4") (pinfunction "Y_4") (pintype "bidirectional"))
    )
    (net (code "99") (name "unconnected-(J3-Pad3V3)") (class "Default")
      (node (ref "J3") (pin "3V3") (pinfunction "3V3_3V3") (pintype "bidirectional"))
    )
    (net (code "100") (name "unconnected-(J3-PadCS)") (class "Default")
      (node (ref "J3") (pin "CS") (pinfunction "CS_CS") (pintype "bidirectional"))
    )
    (net (code "101") (name "unconnected-(J3-PadDC)") (class "Default")
      (node (ref "J3") (pin "DC") (pinfunction "DC_DC") (pintype "bidirectional"))
    )
    (net (code "102") (name "unconnected-(J4-DET_A-PadSW_A)") (class "Default")
      (node (ref "J4") (pin "SW_A") (pinfunction "DET_A_SW_A") (pintype "bidirectional"))
    )
    (net (code "103") (name "unconnected-(J4-DET_B-PadSW_B)") (class "Default")
      (node (ref "J4") (pin "SW_B") (pinfunction "DET_B_SW_B") (pintype "bidirectional"))
    )
    (net (code "104") (name "unconnected-(J4-PadDAT1)") (class "Default")
      (node (ref "J4") (pin "DAT1") (pinfunction "DAT1_DAT1") (pintype "bidirectional"))
    )
    (net (code "105") (name "unconnected-(J4-PadDAT2)") (class "Default")
      (node (ref "J4") (pin "DAT2") (pinfunction "DAT2_DAT2") (pintype "bidirectional"))
    )
    (net (code "106") (name "unconnected-(N1-PA1{slash}ADC1-Pad9)") (class "Default")
      (node (ref "N1") (pin "9") (pinfunction "PA1/ADC1_9") (pintype "bidirectional"))
    )
    (net (code "107") (name "unconnected-(N1-PA3{slash}ADC3-Pad7)") (class "Default")
      (node (ref "N1") (pin "7") (pinfunction "PA3/ADC3_7") (pintype "bidirectional"))
    )
    (net (code "108") (name "unconnected-(N1-PA4{slash}ADC4-Pad6)") (class "Default")
      (node (ref "N1") (pin "6") (pinfunction "PA4/ADC4_6") (pintype "bidirectional"))
    )
    (net (code "109") (name "unconnected-(N1-PB0-Pad11)") (class "Default")
      (node (ref "N1") (pin "11") (pinfunction "PB0_11") (pintype "bidirectional"))
    )
    (net (code "110") (name "unconnected-(N1-PB1-Pad12)") (class "Default")
      (node (ref "N1") (pin "12") (pinfunction "PB1_12") (pintype "bidirectional"))
    )
    (net (code "111") (name "unconnected-(N1-PB2-Pad13)") (class "Default")
      (node (ref "N1") (pin "13") (pinfunction "PB2_13") (pintype "bidirectional"))
    )
    (net (code "112") (name "unconnected-(N1-PD7-Pad22)") (class "Default")
      (node (ref "N1") (pin "22") (pinfunction "PD7_22") (pintype "bidirectional"))
    )
    (net (code "113") (name "unconnected-(N1-VUSB-Pad2)") (class "Default")
      (node (ref "N1") (pin "2") (pinfunction "VUSB_2") (pintype "bidirectional"))
    )
    (net (code "114") (name "unconnected-(N1-~{RST}-Pad34)") (class "Default")
      (node (ref "N1") (pin "34") (pinfunction "~{RST}_34") (pintype "bidirectional"))
    )
    (net (code "115") (name "unconnected-(S1-3-Pad1)") (class "Default")
      (node (ref "S1") (pin "1") (pinfunction "3_1") (pintype "bidirectional"))
    )
    (net (code "116") (name "unconnected-(U1-ADC-PadP$25)") (class "Default")
      (node (ref "U1") (pin "P$25") (pinfunction "ADC_P$25") (pintype "bidirectional"))
    )
    (net (code "117") (name "unconnected-(U1-CTS-PadP$7)") (class "Default")
      (node (ref "U1") (pin "P$7") (pinfunction "CTS_P$7") (pintype "bidirectional"))
    )
    (net (code "118") (name "unconnected-(U1-DCD-PadP$5)") (class "Default")
      (node (ref "U1") (pin "P$5") (pinfunction "DCD_P$5") (pintype "bidirectional"))
    )
    (net (code "119") (name "unconnected-(U1-DTR-PadP$3)") (class "Default")
      (node (ref "U1") (pin "P$3") (pinfunction "DTR_P$3") (pintype "bidirectional"))
    )
    (net (code "120") (name "unconnected-(U1-GPIO1-PadP$40)") (class "Default")
      (node (ref "U1") (pin "P$40") (pinfunction "GPIO1_P$40") (pintype "bidirectional"))
    )
    (net (code "121") (name "unconnected-(U1-GPIO2-PadP$41)") (class "Default")
      (node (ref "U1") (pin "P$41") (pinfunction "GPIO2_P$41") (pintype "bidirectional"))
    )
    (net (code "122") (name "unconnected-(U1-GPIO3-PadP$42)") (class "Default")
      (node (ref "U1") (pin "P$42") (pinfunction "GPIO3_P$42") (pintype "bidirectional"))
    )
    (net (code "123") (name "unconnected-(U1-GPIO4-PadP$43)") (class "Default")
      (node (ref "U1") (pin "P$43") (pinfunction "GPIO4_P$43") (pintype "bidirectional"))
    )
    (net (code "124") (name "unconnected-(U1-GPIO6-PadP$47)") (class "Default")
      (node (ref "U1") (pin "P$47") (pinfunction "GPIO6_P$47") (pintype "bidirectional"))
    )
    (net (code "125") (name "unconnected-(U1-GPIO7-PadP$48)") (class "Default")
      (node (ref "U1") (pin "P$48") (pinfunction "GPIO7_P$48") (pintype "bidirectional"))
    )
    (net (code "126") (name "unconnected-(U1-GPIO8{slash}DBG_RXD-PadP$49)") (class "Default")
      (node (ref "U1") (pin "P$49") (pinfunction "GPIO8/DBG_RXD_P$49") (pintype "bidirectional"))
    )
    (net (code "127") (name "unconnected-(U1-GPIO9{slash}DBG_TXD-PadP$50)") (class "Default")
      (node (ref "U1") (pin "P$50") (pinfunction "GPIO9/DBG_TXD_P$50") (pintype "bidirectional"))
    )
    (net (code "128") (name "unconnected-(U1-GPIO11-PadP$67)") (class "Default")
      (node (ref "U1") (pin "P$67") (pinfunction "GPIO11_P$67") (pintype "bidirectional"))
    )
    (net (code "129") (name "unconnected-(U1-GPIO12-PadP$68)") (class "Default")
      (node (ref "U1") (pin "P$68") (pinfunction "GPIO12_P$68") (pintype "bidirectional"))
    )
    (net (code "130") (name "unconnected-(U1-NETLIGHT-PadP$52)") (class "Default")
      (node (ref "U1") (pin "P$52") (pinfunction "NETLIGHT_P$52") (pintype "bidirectional"))
    )
    (net (code "131") (name "unconnected-(U1-PWM1-PadP$35)") (class "Default")
      (node (ref "U1") (pin "P$35") (pinfunction "PWM1_P$35") (pintype "bidirectional"))
    )
    (net (code "132") (name "unconnected-(U1-PWM2-PadP$36)") (class "Default")
      (node (ref "U1") (pin "P$36") (pinfunction "PWM2_P$36") (pintype "bidirectional"))
    )
    (net (code "133") (name "unconnected-(U1-RESET-PadP$16)") (class "Default")
      (node (ref "U1") (pin "P$16") (pinfunction "RESET_P$16") (pintype "bidirectional"))
    )
    (net (code "134") (name "unconnected-(U1-RTS-PadP$8)") (class "Default")
      (node (ref "U1") (pin "P$8") (pinfunction "RTS_P$8") (pintype "bidirectional"))
    )
    (net (code "135") (name "unconnected-(U1-SCL-PadP$38)") (class "Default")
      (node (ref "U1") (pin "P$38") (pinfunction "SCL_P$38") (pintype "bidirectional"))
    )
    (net (code "136") (name "unconnected-(U1-SDA-PadP$37)") (class "Default")
      (node (ref "U1") (pin "P$37") (pinfunction "SDA_P$37") (pintype "bidirectional"))
    )
    (net (code "137") (name "unconnected-(U1-SPI_CLK-PadP$11)") (class "Default")
      (node (ref "U1") (pin "P$11") (pinfunction "SPI_CLK_P$11") (pintype "bidirectional"))
    )
    (net (code "138") (name "unconnected-(U1-SPI_CS-PadP$14)") (class "Default")
      (node (ref "U1") (pin "P$14") (pinfunction "SPI_CS_P$14") (pintype "bidirectional"))
    )
    (net (code "139") (name "unconnected-(U1-SPI_MISO-PadP$13)") (class "Default")
      (node (ref "U1") (pin "P$13") (pinfunction "SPI_MISO_P$13") (pintype "bidirectional"))
    )
    (net (code "140") (name "unconnected-(U1-SPI_MOSI-PadP$12)") (class "Default")
      (node (ref "U1") (pin "P$12") (pinfunction "SPI_MOSI_P$12") (pintype "bidirectional"))
    )
    (net (code "141") (name "unconnected-(U1-USB_DN-PadP$28)") (class "Default")
      (node (ref "U1") (pin "P$28") (pinfunction "USB_DN_P$28") (pintype "bidirectional"))
    )
    (net (code "142") (name "unconnected-(U1-USB_DP-PadP$27)") (class "Default")
      (node (ref "U1") (pin "P$27") (pinfunction "USB_DP_P$27") (pintype "bidirectional"))
    )
    (net (code "143") (name "unconnected-(U1-USIM_DET-PadP$34)") (class "Default")
      (node (ref "U1") (pin "P$34") (pinfunction "USIM_DET_P$34") (pintype "bidirectional"))
    )
    (net (code "144") (name "unconnected-(U1-VBUS-PadP$24)") (class "Default")
      (node (ref "U1") (pin "P$24") (pinfunction "VBUS_P$24") (pintype "bidirectional"))
    )
    (net (code "145") (name "unconnected-(U1-VRTC-PadP$26)") (class "Default")
      (node (ref "U1") (pin "P$26") (pinfunction "VRTC_P$26") (pintype "bidirectional"))
    )
    (net (code "146") (name "unconnected-(U3-INT-Pad7)") (class "Default")
      (node (ref "U3") (pin "7") (pinfunction "INT_7") (pintype "bidirectional"))
    )
    (net (code "147") (name "unconnected-(U4-INT-Pad7)") (class "Default")
      (node (ref "U4") (pin "7") (pinfunction "INT_7") (pintype "bidirectional"))
    )
    (net (code "148") (name "unconnected-(U5-GP5-Pad14)") (class "Default")
      (node (ref "U5") (pin "14") (pinfunction "GP5_14") (pintype "bidirectional"))
    )
    (net (code "149") (name "unconnected-(U5-GP6-Pad15)") (class "Default")
      (node (ref "U5") (pin "15") (pinfunction "GP6_15") (pintype "bidirectional"))
    )
    (net (code "150") (name "unconnected-(U5-GP7-Pad16)") (class "Default")
      (node (ref "U5") (pin "16") (pinfunction "GP7_16") (pintype "bidirectional"))
    )
    (net (code "151") (name "unconnected-(U5-INT-Pad7)") (class "Default")
      (node (ref "U5") (pin "7") (pinfunction "INT_7") (pintype "bidirectional"))
    )
    (net (code "152") (name "unconnected-(U8-VPP-PadC6)") (class "Default")
      (node (ref "U8") (pin "C6") (pinfunction "VPP_C6") (pintype "bidirectional"))
    )
    (net (code "153") (name "unconnected-(U9-X1-PadP$1)") (class "Default")
      (node (ref "U9") (pin "P$1") (pinfunction "X1_P$1") (pintype "bidirectional"))
    )
    (net (code "154") (name "unconnected-(U10-NC-Pad4)") (class "Default")
      (node (ref "U10") (pin "4") (pinfunction "NC_4") (pintype "bidirectional"))
    )
    (net (code "155") (name "unconnected-(U11-NC-Pad2)") (class "Default")
      (node (ref "U11") (pin "2") (pinfunction "NC_2") (pintype "bidirectional"))
    )
    (net (code "156") (name "unconnected-(U11-PG-Pad3)") (class "Default")
      (node (ref "U11") (pin "3") (pinfunction "PG_3") (pintype "bidirectional"))
    )
    (net (code "157") (name "unconnected-(U15-NC-Pad4)") (class "Default")
      (node (ref "U15") (pin "4") (pinfunction "NC_4") (pintype "bidirectional"))
    )
  )
)
